# WX0_008_941DL.net
KiCad netlist of a schematic drawn in Altium Designer
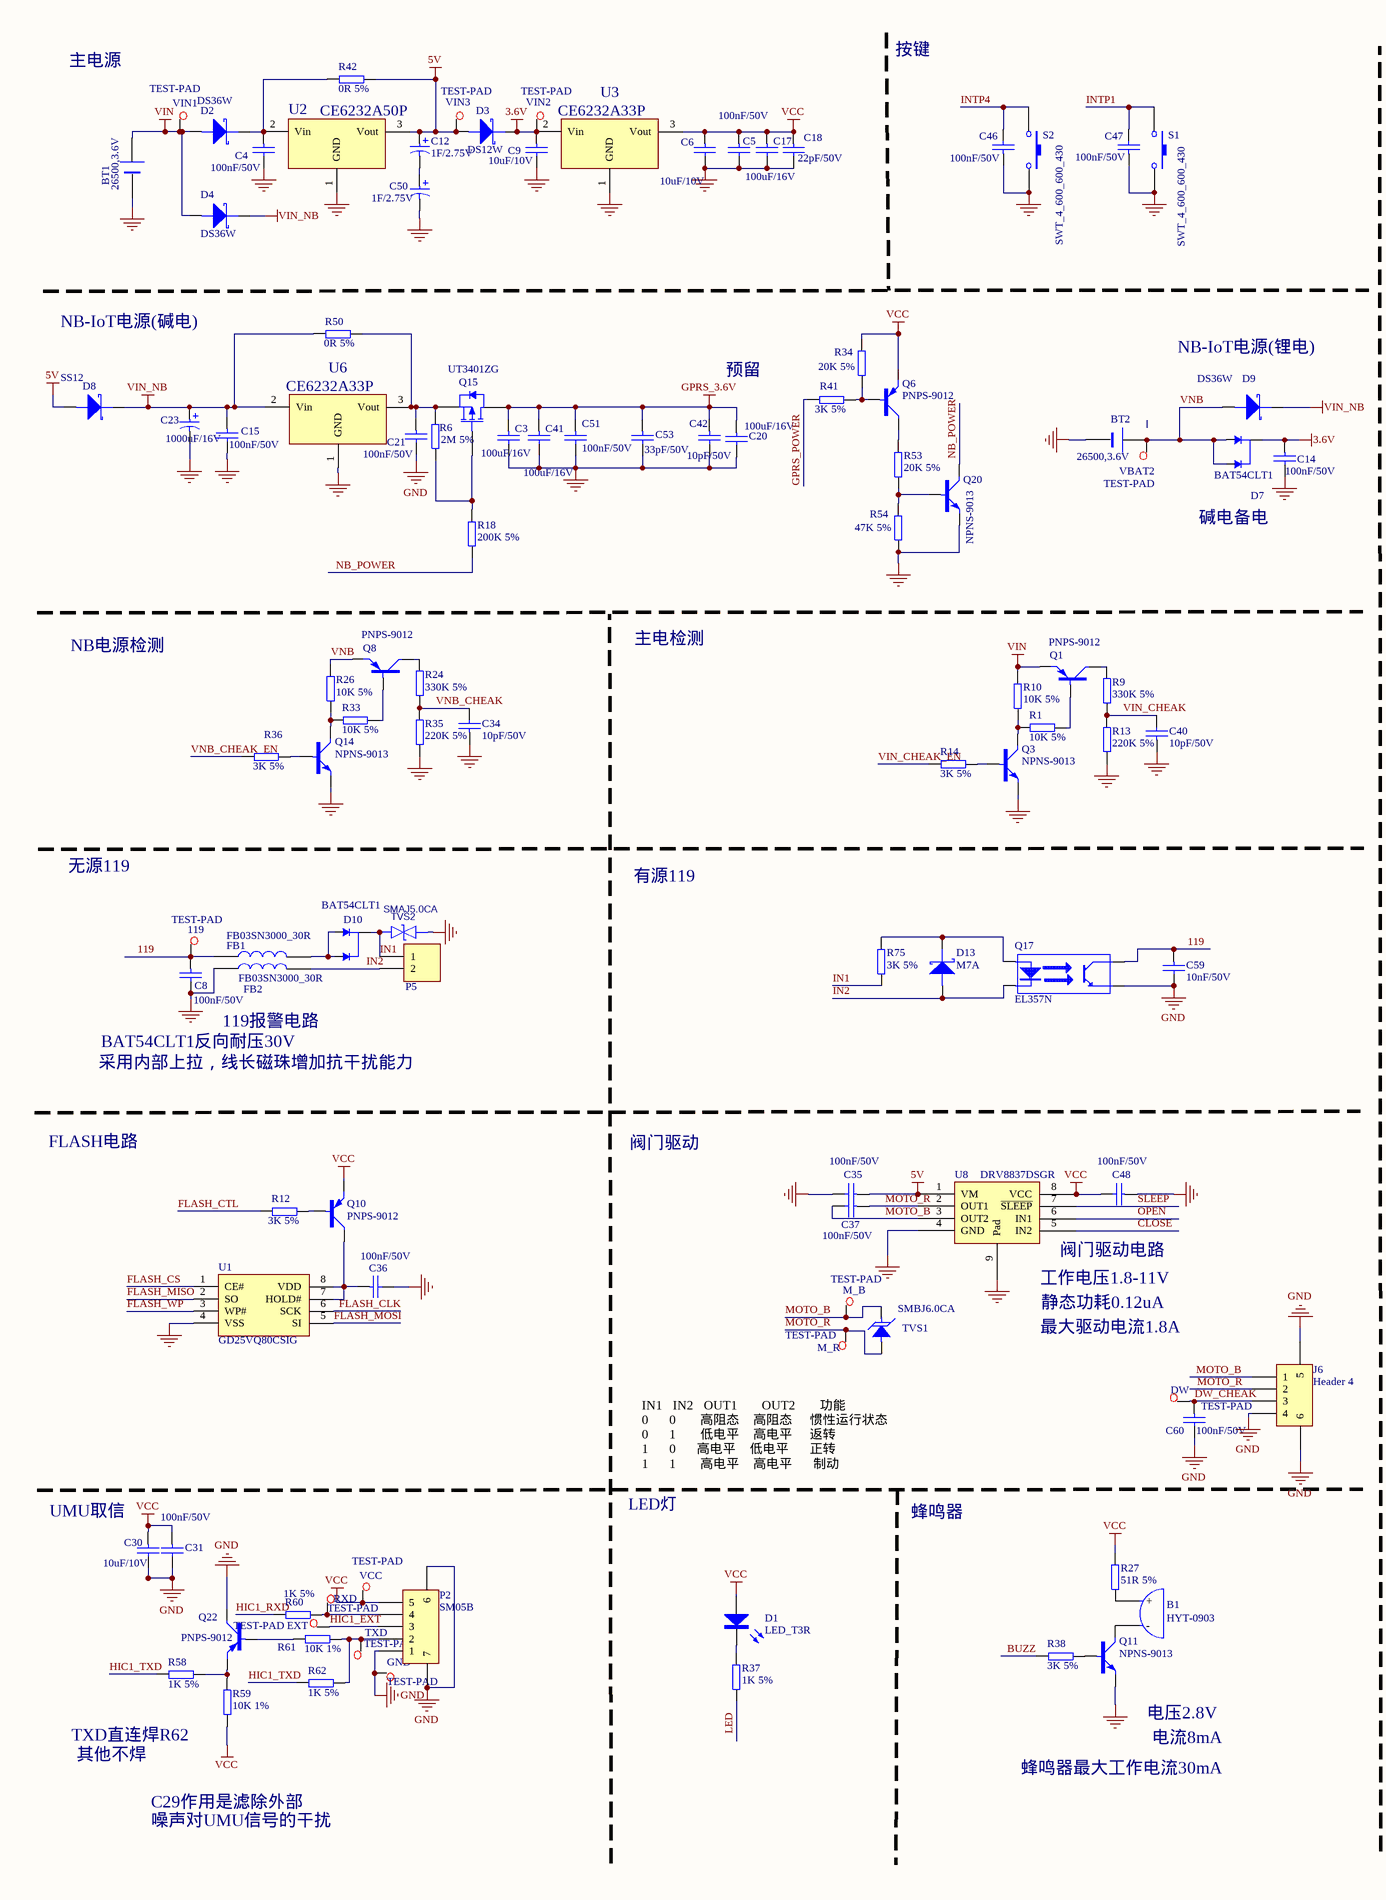
[diagram p0: WX0.008.941DL.SchDoc, left]
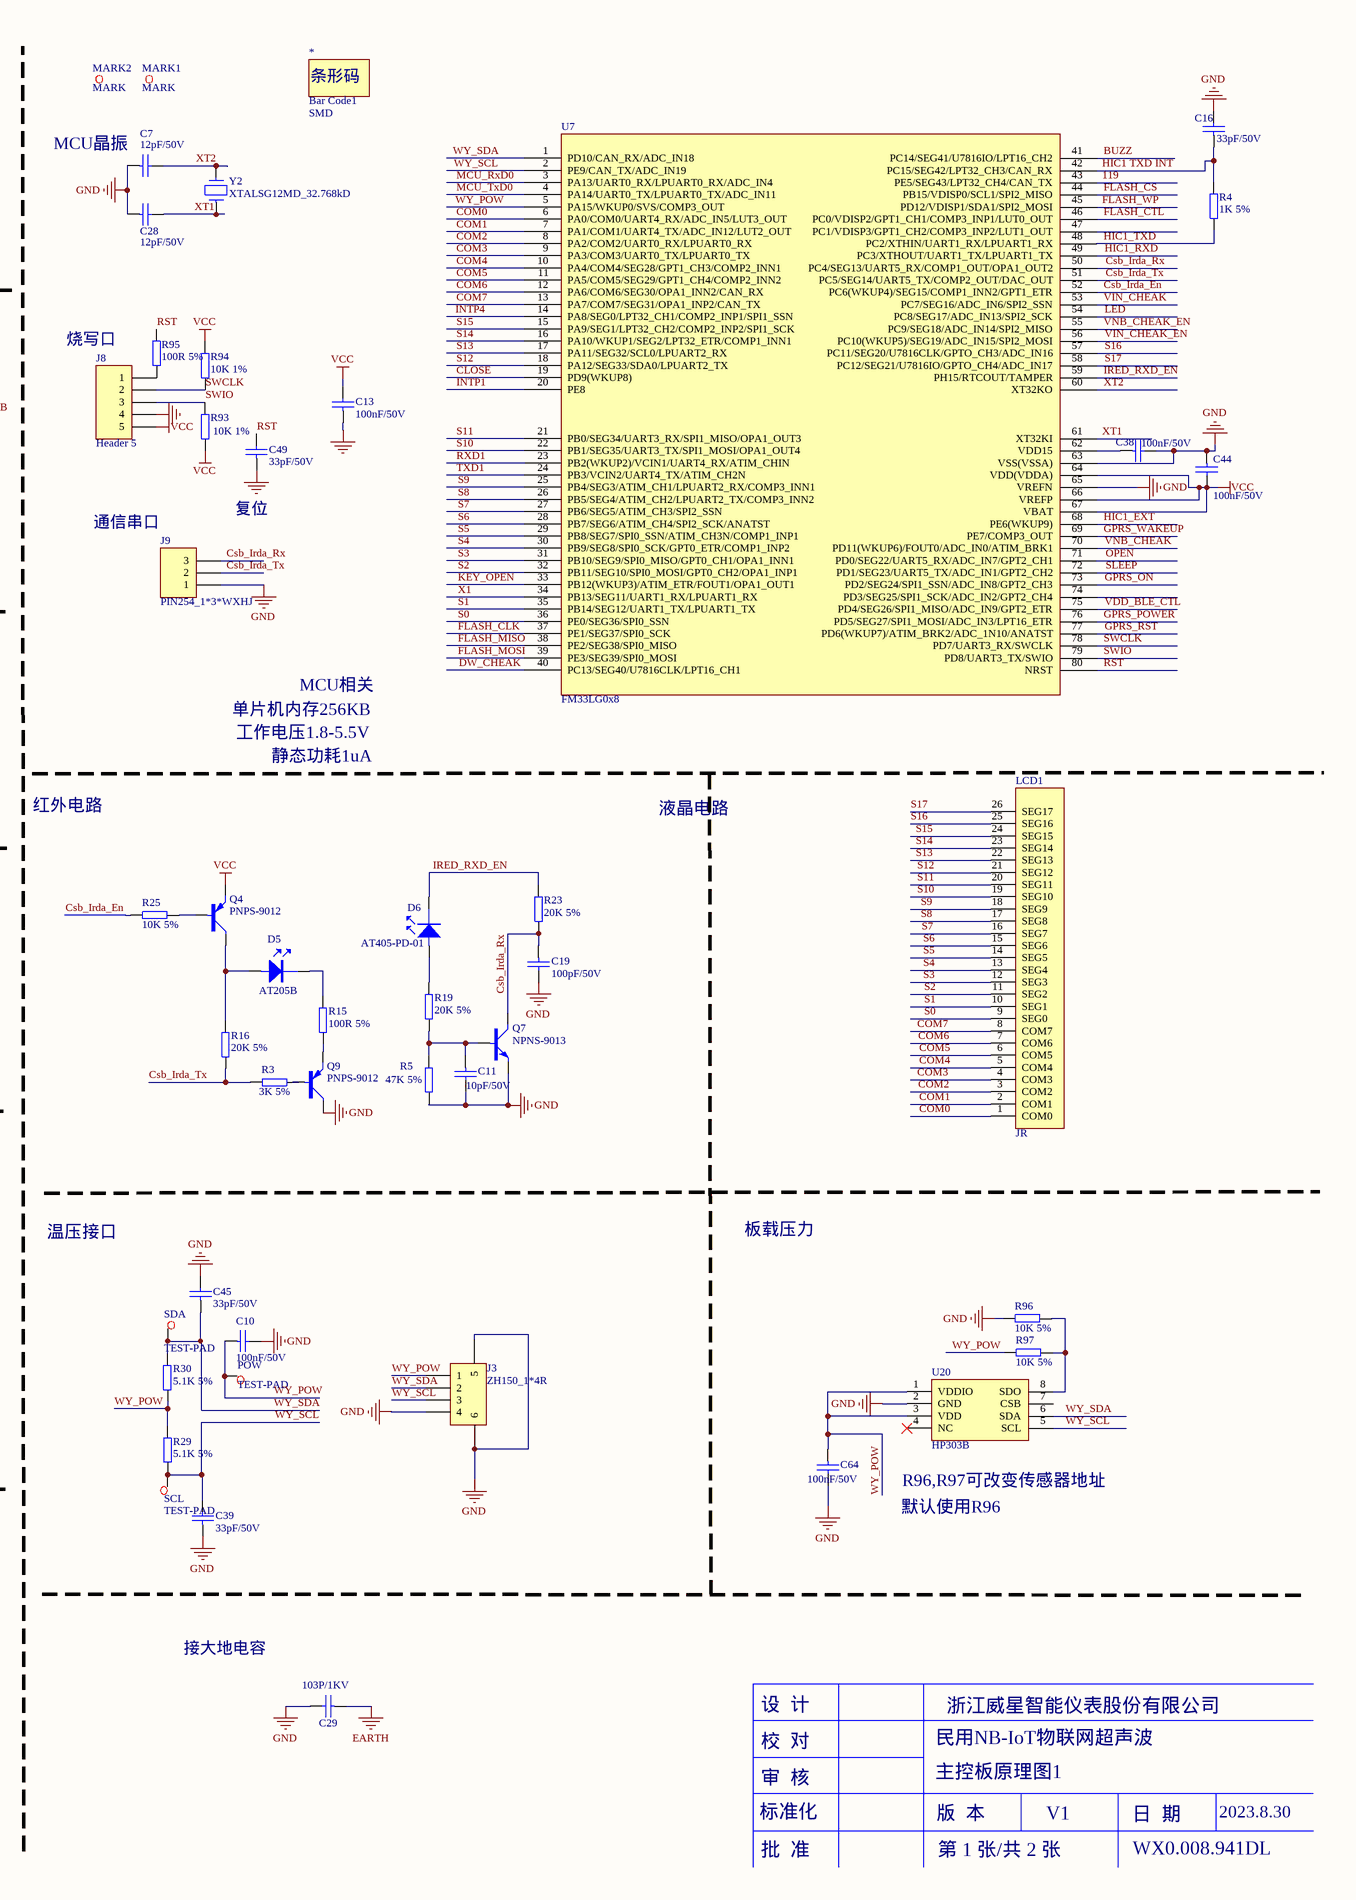
[diagram p1: WX0.008.941DL.SchDoc, right]

(export (version "E")
  (design (tool "Eeschema 10.0.6"))
  (components
    (comp (ref "*")
      (value "Bar Code1")
      (footprint "Bar Code1")
      (description "条形码 ,填充，无需焊接器件")
      (fields (field (name "PART NUMBER") "AD_WXHJ_Bar Code_02") (field (name "SMD/DIP") "SMD"))
      (libsource (lib "Database_Libs2") (part "05_AD_WXHJ_Bar Code_02"))
    )
    (comp (ref "119")
      (value "TEST-PAD")
      (footprint "TEST-PAD")
      (description "单面焊盘测试点")
      (fields (field (name "PART NUMBER") "AD_WXHJ_TEST-PAD_01"))
      (libsource (lib "Database_Libs2") (part "TEST-PAD"))
    )
    (comp (ref "B1")
      (value "HYT-0903")
      (footprint "HYT-0903")
      (description "直插,直径9mm,高5.5mm,5 V,2 V,30 mA,兴化市华宇电子有限公司,HYT-0903")
      (fields (field (name "PART NUMBER") "1010602-0007"))
      (libsource (lib "Database_Libs2") (part "07_HYT-0903"))
    )
    (comp (ref "BT1")
      (value "26500,3.6V")
      (footprint "BATFOOT")
      (description "Battery")
      (libsource (lib "*") (part "BATTERY_1"))
    )
    (comp (ref "BT2")
      (value "26500,3.6V")
      (footprint "BATFOOT")
      (description "Battery")
      (libsource (lib "*") (part "BATTERY_1"))
    )
    (comp (ref "C3")
      (value "100uF/16V")
      (footprint "GRM31CR60J107ME39L")
      (description "100u,16 V,±10%,1206,国巨,CC1206KRNPO7BN106P")
      (libsource (lib "Database_Libs2") (part "CC06KPO7_106P"))
    )
    (comp (ref "C4")
      (value "100nF/50V")
      (footprint "CAP0603")
      (description "104pF,50 V,±10%,0603,国巨,CC0603KRX7R9BB104")
      (fields (field (name "PART NUMBER") "101020103-0021"))
      (libsource (lib "Database_Libs2") (part "CC03K7R9_100N"))
    )
    (comp (ref "C5")
      (value "100nF/50V")
      (footprint "CAP0603")
      (description "104pF,50 V,±10%,0603,国巨,CC0603KRX7R9BB104")
      (fields (field (name "PART NUMBER") "101020103-0021"))
      (libsource (lib "Database_Libs2") (part "CC03K7R9_100N"))
    )
    (comp (ref "C6")
      (value "10uF/10V")
      (footprint "CAP0603")
      (description "106pF,10 V,±10%,0603,村田,GRM188R61A106KE47D")
      (fields (field (name "PART NUMBER") "101020103-0026"))
      (libsource (lib "Database_Libs2") (part "CC03K5R6_10U"))
    )
    (comp (ref "C7")
      (value "12pF/50V")
      (footprint "CAP0603")
      (description "12P,50 V,±5%,0603,国巨,CC0603JRNPO9BN12")
      (fields (field (name "PART NUMBER") "101020103-0005"))
      (libsource (lib "Database_Libs2") (part "CC03JPO9_12P"))
    )
    (comp (ref "C8")
      (value "100nF/50V")
      (footprint "CAP0603")
      (description "104pF,50 V,±10%,0603,国巨,CC0603KRX7R9BB104")
      (fields (field (name "PART NUMBER") "101020103-0021"))
      (libsource (lib "Database_Libs2") (part "CC03K7R9_100N"))
    )
    (comp (ref "C9")
      (value "10uF/10V")
      (footprint "CAP0603")
      (description "106pF,10 V,±10%,0603,村田,GRM188R61A106KE47D")
      (fields (field (name "PART NUMBER") "101020103-0026"))
      (libsource (lib "Database_Libs2") (part "CC03K5R6_10U"))
    )
    (comp (ref "C10")
      (value "100nF/50V")
      (footprint "CAP0603")
      (description "104pF,50 V,±10%,0603,国巨,CC0603KRX7R9BB104")
      (fields (field (name "PART NUMBER") "101020103-0021"))
      (libsource (lib "Database_Libs2") (part "CC03K7R9_100N"))
    )
    (comp (ref "C11")
      (value "10pF/50V")
      (footprint "CAP0603")
      (description "10pF,50 V,±5%,0603,X7R,国巨,CC0603JRNPO9BN100")
      (fields (field (name "PART NUMBER") "101020103-0014"))
      (libsource (lib "Database_Libs2") (part "CC03JPO9_10P"))
    )
    (comp (ref "C12")
      (value "1F/2.75V")
      (footprint "C-SUP-4P-H - L")
      (description "1F,2.75 V,-20%~+20%,8mm*16mm,红宝石,2.7 DMC 1 M MY4 8X16")
      (fields (field (name "PART NUMBER") "1010202-0015"))
      (libsource (lib "Database_Libs2") (part "CALM3MRDMC_1F"))
    )
    (comp (ref "C13")
      (value "100nF/50V")
      (footprint "CAP0603")
      (description "104pF,50 V,±10%,0603,国巨,CC0603KRX7R9BB104")
      (fields (field (name "PART NUMBER") "101020103-0021"))
      (libsource (lib "Database_Libs2") (part "CC03K7R9_100N"))
    )
    (comp (ref "C14")
      (value "100nF/50V")
      (footprint "CAP0603")
      (description "104pF,50 V,±10%,0603,国巨,CC0603KRX7R9BB104")
      (fields (field (name "PART NUMBER") "101020103-0021"))
      (libsource (lib "Database_Libs2") (part "CC03K7R9_100N"))
    )
    (comp (ref "C15")
      (value "100nF/50V")
      (footprint "CAP0603")
      (description "104pF,50 V,±10%,0603,国巨,CC0603KRX7R9BB104")
      (fields (field (name "PART NUMBER") "101020103-0021"))
      (libsource (lib "Database_Libs2") (part "CC03K7R9_100N"))
    )
    (comp (ref "C16")
      (value "33pF/50V")
      (footprint "CAP0603")
      (description "33pF,50 V,±10%,0603,国巨,CC0603KRNPO9BN33")
      (fields (field (name "PART NUMBER") "101020103-0027"))
      (libsource (lib "Database_Libs2") (part "CC03KPO9_33P"))
    )
    (comp (ref "C17")
      (value "100uF/16V")
      (footprint "GRM31CR60J107ME39L")
      (description "100u,16 V,±10%,1206,国巨,CC1206KRNPO7BN106P")
      (libsource (lib "Database_Libs2") (part "CC06KPO7_106P"))
    )
    (comp (ref "C18")
      (value "22pF/50V")
      (footprint "CAP0603")
      (description "22pF,50 V,±5%,0603,国巨,CC0603JRNPO9BN22")
      (fields (field (name "PART NUMBER") "101020103-0009"))
      (libsource (lib "Database_Libs2") (part "CC03JPO9_22P"))
    )
    (comp (ref "C19")
      (value "100pF/50V")
      (footprint "CAP0603")
      (description "101pf,50 V,±5%,0603,国巨,CC0603JRNP09BN101")
      (fields (field (name "PART NUMBER") "101020103-0010"))
      (libsource (lib "Database_Libs2") (part "CC03JPO9_101P"))
    )
    (comp (ref "C20")
      (value "100uF/16V")
      (footprint "GRM31CR60J107ME39L")
      (libsource (lib "Database_Libs2") (part "CC06KPO7_106P"))
    )
    (comp (ref "C21")
      (value "100nF/50V")
      (footprint "CAP0603")
      (description "104pF,50 V,±10%,0603,国巨,CC0603KRX7R9BB104")
      (fields (field (name "PART NUMBER") "101020103-0021"))
      (libsource (lib "Database_Libs2") (part "CC03K7R9_100N"))
    )
    (comp (ref "C23")
      (value "1000uF/16V")
      (footprint "CAPPC_500_800_2000R")
      (description "1000UF,16V,±20%,贴片10*10.2MM,深圳市三炎科电子科技有限公司,16V1000UF")
      (fields (field (name "PART NUMBER") "1010203-0026"))
      (libsource (lib "Database_Libs2") (part "CAL7MRZLH_1000U_R"))
    )
    (comp (ref "C28")
      (value "12pF/50V")
      (footprint "CAP0603")
      (description "12P,50 V,±5%,0603,国巨,CC0603JRNPO9BN12")
      (fields (field (name "PART NUMBER") "101020103-0005"))
      (libsource (lib "Database_Libs2") (part "CC03JPO9_12P"))
    )
    (comp (ref "C29")
      (value "103P/1KV")
      (footprint "CAP1206")
      (description "103P/1KV,±10％,1206")
      (fields (field (name "PART NUMBER") "101020101-0003"))
      (libsource (lib "altium-import") (part "root_3_CC03K7R9_100N_"))
    )
    (comp (ref "C30")
      (value "10uF/10V")
      (footprint "CAP0603")
      (description "106pF,10 V,±10%,0603,村田,GRM188R61A106KE47D")
      (fields (field (name "PART NUMBER") "101020103-0026"))
      (libsource (lib "Database_Libs2") (part "CC03K5R6_10U"))
    )
    (comp (ref "C31")
      (value "100nF/50V")
      (footprint "CAP0603")
      (description "104pF,50 V,±10%,0603,国巨,CC0603KRX7R9BB104")
      (fields (field (name "PART NUMBER") "101020103-0021"))
      (libsource (lib "Database_Libs2") (part "CC03K7R9_100N"))
    )
    (comp (ref "C34")
      (value "10pF/50V")
      (footprint "CAP0603")
      (description "10pF,50 V,±5%,0603,X7R,国巨,CC0603JRNPO9BN100")
      (fields (field (name "PART NUMBER") "101020103-0014"))
      (libsource (lib "Database_Libs2") (part "CC03JPO9_10P"))
    )
    (comp (ref "C35")
      (value "100nF/50V")
      (footprint "CAP0603")
      (description "104pF,50 V,±10%,0603,国巨,CC0603KRX7R9BB104")
      (fields (field (name "PART NUMBER") "101020103-0021"))
      (libsource (lib "Database_Libs2") (part "CC03K7R9_100N"))
    )
    (comp (ref "C36")
      (value "100nF/50V")
      (footprint "CAP0603")
      (description "104pF,50 V,±10%,0603,国巨,CC0603KRX7R9BB104")
      (fields (field (name "PART NUMBER") "101020103-0021"))
      (libsource (lib "Database_Libs2") (part "CC03K7R9_100N"))
    )
    (comp (ref "C37")
      (value "100nF/50V")
      (footprint "CAP0603")
      (description "104pF,50 V,±10%,0603,国巨,CC0603KRX7R9BB104")
      (fields (field (name "PART NUMBER") "101020103-0021"))
      (libsource (lib "Database_Libs2") (part "CC03K7R9_100N"))
    )
    (comp (ref "C38")
      (value "100nF/50V")
      (footprint "CAP0603")
      (description "104pF,50 V,±10%,0603,国巨,CC0603KRX7R9BB104")
      (fields (field (name "PART NUMBER") "101020103-0021"))
      (libsource (lib "Database_Libs2") (part "CC03K7R9_100N"))
    )
    (comp (ref "C39")
      (value "33pF/50V")
      (footprint "CAP0603")
      (description "33pF,50 V,±10%,0603,国巨,CC0603KRNPO9BN33")
      (fields (field (name "PART NUMBER") "101020103-0027"))
      (libsource (lib "Database_Libs2") (part "CC03KPO9_33P"))
    )
    (comp (ref "C40")
      (value "10pF/50V")
      (footprint "CAP0603")
      (description "10pF,50 V,±5%,0603,X7R,国巨,CC0603JRNPO9BN100")
      (fields (field (name "PART NUMBER") "101020103-0014"))
      (libsource (lib "Database_Libs2") (part "CC03JPO9_10P"))
    )
    (comp (ref "C41")
      (value "100uF/16V")
      (footprint "GRM31CR60J107ME39L")
      (description "100u,16 V,±10%,1206,国巨,CC1206KRNPO7BN106P")
      (libsource (lib "Database_Libs2") (part "CC06KPO7_106P"))
    )
    (comp (ref "C42")
      (value "10pF/50V")
      (footprint "CAP0603")
      (description "10pF,50 V,±5%,0603,X7R,国巨,CC0603JRNPO9BN100")
      (fields (field (name "PART NUMBER") "101020103-0014"))
      (libsource (lib "Database_Libs2") (part "CC03JPO9_10P"))
    )
    (comp (ref "C44")
      (value "100nF/50V")
      (footprint "CAP0603")
      (description "104pF,50 V,±10%,0603,国巨,CC0603KRX7R9BB104")
      (fields (field (name "PART NUMBER") "101020103-0021"))
      (libsource (lib "Database_Libs2") (part "CC03K7R9_100N"))
    )
    (comp (ref "C45")
      (value "33pF/50V")
      (footprint "CAP0603")
      (description "33pF,50 V,±10%,0603,国巨,CC0603KRNPO9BN33")
      (fields (field (name "PART NUMBER") "101020103-0027"))
      (libsource (lib "Database_Libs2") (part "CC03KPO9_33P"))
    )
    (comp (ref "C46")
      (value "100nF/50V")
      (footprint "CAP0603")
      (description "104pF,50 V,±10%,0603,国巨,CC0603KRX7R9BB104")
      (fields (field (name "PART NUMBER") "101020103-0021"))
      (libsource (lib "Database_Libs2") (part "CC03K7R9_100N"))
    )
    (comp (ref "C47")
      (value "100nF/50V")
      (footprint "CAP0603")
      (description "104pF,50 V,±10%,0603,国巨,CC0603KRX7R9BB104")
      (fields (field (name "PART NUMBER") "101020103-0021"))
      (libsource (lib "Database_Libs2") (part "CC03K7R9_100N"))
    )
    (comp (ref "C48")
      (value "100nF/50V")
      (footprint "CAP0603")
      (description "104pF,50 V,±10%,0603,国巨,CC0603KRX7R9BB104")
      (fields (field (name "PART NUMBER") "101020103-0021"))
      (libsource (lib "Database_Libs2") (part "CC03K7R9_100N"))
    )
    (comp (ref "C49")
      (value "33pF/50V")
      (footprint "CAP0603")
      (description "33pF,50 V,±10%,0603,国巨,CC0603KRNPO9BN33")
      (fields (field (name "PART NUMBER") "101020103-0027"))
      (libsource (lib "Database_Libs2") (part "CC03KPO9_33P"))
    )
    (comp (ref "C50")
      (value "1F/2.75V")
      (footprint "C-SUP-4P-H - L")
      (description "1F,2.75 V,-20%~+20%,8mm*16mm,红宝石,2.7 DMC 1 M MY4 8X16")
      (fields (field (name "PART NUMBER") "1010202-0015"))
      (libsource (lib "Database_Libs2") (part "CALM3MRDMC_1F"))
    )
    (comp (ref "C51")
      (value "100nF/50V")
      (footprint "CAP0603")
      (description "104pF,50 V,±10%,0603,国巨,CC0603KRX7R9BB104")
      (fields (field (name "PART NUMBER") "101020103-0021"))
      (libsource (lib "Database_Libs2") (part "CC03K7R9_100N"))
    )
    (comp (ref "C53")
      (value "33pF/50V")
      (footprint "CAP0603")
      (description "33pF,50 V,±10%,0603,国巨,CC0603KRNPO9BN33")
      (fields (field (name "PART NUMBER") "101020103-0027"))
      (libsource (lib "Database_Libs2") (part "CC03KPO9_33P"))
    )
    (comp (ref "C59")
      (value "10nF/50V")
      (footprint "CAP0603")
      (description "10nF,50 V,±10%,0603,X7R,国巨,CC0603KRX7R9BB103")
      (fields (field (name "PART NUMBER") "101020103-0007"))
      (libsource (lib "Database_Libs2") (part "CC03K7R9_103P"))
    )
    (comp (ref "C60")
      (value "100nF/50V")
      (footprint "CAP0603")
      (description "104pF,50 V,±10%,0603,国巨,CC0603KRX7R9BB104")
      (fields (field (name "PART NUMBER") "101020103-0021"))
      (libsource (lib "Database_Libs2") (part "CC03K7R9_100N"))
    )
    (comp (ref "C64")
      (value "100nF/50V")
      (footprint "CAP0603")
      (description "104pF,50 V,±10%,0603,国巨,CC0603KRX7R9BB104")
      (fields (field (name "PART NUMBER") "101020103-0021"))
      (libsource (lib "Database_Libs2") (part "CC03K7R9_100N"))
    )
    (comp (ref "D1")
      (value "LED_T3R")
      (footprint "LED3")
      (description "圆形插件,3mm 圆形,插件,红光,湖北匡通电子有限公司,3BB4HC")
      (fields (field (name "PART NUMBER") "101040102-0001"))
      (libsource (lib "Database_Libs2") (part "01-LED_T3R"))
    )
    (comp (ref "D2")
      (value "DS36W")
      (footprint "SOD-123FL")
      (description "DS36W,SOD123-FL,3 A,42 V,60 V,浙江领晨科技有限公司,DS36W")
      (fields (field (name "PART NUMBER") "101040101-0055"))
      (libsource (lib "Database_Libs2") (part "02_DS12W"))
    )
    (comp (ref "D3")
      (value "DS12W")
      (footprint "SOD-123FL")
      (description "DS12W,SOD-123FL,1 A,0.55 V,20 V,领晨科技,DS12W")
      (fields (field (name "PART NUMBER") "101040101-0048"))
      (libsource (lib "Database_Libs2") (part "02_DS12W"))
    )
    (comp (ref "D4")
      (value "DS36W")
      (footprint "SOD-123FL")
      (description "DS36W,SOD123-FL,3 A,42 V,60 V,浙江领晨科技有限公司,DS36W")
      (fields (field (name "PART NUMBER") "101040101-0055"))
      (libsource (lib "Database_Libs2") (part "02_DS36W"))
    )
    (comp (ref "D5")
      (value "AT205B")
      (footprint "IR_254_1000_500")
      (description "直插,Φ5.8mm圆头透明色，,0.1 A,4 V,5 V,上海品观电子有限公司,AT205B")
      (fields (field (name "PART NUMBER") "101040101-0034"))
      (libsource (lib "Database_Libs2") (part "01_AT205B"))
    )
    (comp (ref "D6")
      (value "AT405-PD-01")
      (footprint "IR_254_1000_500")
      (description "Φ5.8mm圆头黑色，光电接收管,Φ5.8mm,0.01 A,1.2 V,60 V,上海品观电子,AT405-PD-01")
      (fields (field (name "PART NUMBER") "101040101-0035"))
      (libsource (lib "Database_Libs2") (part "01_AT405-PD-01"))
    )
    (comp (ref "D7")
      (value "BAT54CLT1")
      (footprint "SOT-23")
      (description "BAT54CLT1，SOT23-3,SOT23-3,0.2 A,0.8 V,30 V,安森美,BAT54CLT1")
      (fields (field (name "PART NUMBER") "101040101-0038"))
      (libsource (lib "Database_Libs2") (part "02_BAT54CLT1"))
    )
    (comp (ref "D8")
      (value "SS12")
      (footprint "DO-214AC")
      (description "SS12,DO-214AC,1 A,0.55 V,20 V,昶鑫,SS12")
      (fields (field (name "PART NUMBER") "101040101-0009"))
      (libsource (lib "Database_Libs2") (part "02_SS12"))
    )
    (comp (ref "D9")
      (value "DS36W")
      (footprint "SOD-123FL")
      (description "DS36W,SOD123-FL,3 A,42 V,60 V,浙江领晨科技有限公司,DS36W")
      (fields (field (name "PART NUMBER") "101040101-0055"))
      (libsource (lib "Database_Libs2") (part "02_DS36W"))
    )
    (comp (ref "D10")
      (value "BAT54CLT1")
      (footprint "SOT-23")
      (description "BAT54CLT1，SOT23-3,SOT23-3,0.2 A,0.8 V,30 V,安森美,BAT54CLT1")
      (fields (field (name "PART NUMBER") "101040101-0038"))
      (libsource (lib "Database_Libs2") (part "02_BAT54CLT1"))
    )
    (comp (ref "D13")
      (value "M7A")
      (footprint "DO-214AC")
      (description "M7A,DO-214AC,1 A,1.1 V,1000 V,杭州闽达电子有限公司,M7A")
      (fields (field (name "PART NUMBER") "101040101-0008"))
      (libsource (lib "Database_Libs2") (part "02_M7A"))
    )
    (comp (ref "DW")
      (value "TEST-PAD")
      (footprint "TEST-PAD")
      (description "单面焊盘测试点")
      (fields (field (name "PART NUMBER") "AD_WXHJ_TEST-PAD_01"))
      (libsource (lib "Database_Libs2") (part "TEST-PAD"))
    )
    (comp (ref "EXT")
      (value "TEST-PAD")
      (footprint "TEST-PAD")
      (description "单面焊盘测试点")
      (fields (field (name "PART NUMBER") "AD_WXHJ_TEST-PAD_01"))
      (libsource (lib "Database_Libs2") (part "TEST-PAD"))
    )
    (comp (ref "FB1")
      (value "FB03SN3000_30R")
      (footprint "IND0603")
      (description "chilisin(奇力新),0603,30Ω ±25% @100MHz,150 V,125 ℃,PBY160808T-300Y-N,-55 ℃,不含铅,,,圆盘,30Ω ±25% @100MHz")
      (fields (field (name "PART NUMBER") "109010101-0003"))
      (libsource (lib "Database_Libs2") (part "06_FB03SN3000_30R"))
    )
    (comp (ref "FB2")
      (value "FB03SN3000_30R")
      (footprint "IND0603")
      (description "chilisin(奇力新),0603,30Ω ±25% @100MHz,150 V,125 ℃,PBY160808T-300Y-N,-55 ℃,不含铅,,,圆盘,30Ω ±25% @100MHz")
      (fields (field (name "PART NUMBER") "109010101-0003"))
      (libsource (lib "Database_Libs2") (part "06_FB03SN3000_30R"))
    )
    (comp (ref "GND")
      (value "TEST-PAD")
      (footprint "TEST-PAD")
      (description "单面焊盘测试点")
      (fields (field (name "PART NUMBER") "AD_WXHJ_TEST-PAD_01"))
      (libsource (lib "Database_Libs2") (part "TEST-PAD"))
    )
    (comp (ref "J3")
      (value "ZH150_1*4R")
      (footprint "SMT-1.5-4")
      (description "4针1.5mm间距，贴片卧式,9.0mm*6.5mm,公头,单排,4针1.5mm间距，贴片卧式")
      (fields (field (name "PART NUMBER") "1010902-0126"))
      (libsource (lib "Database_Libs2") (part "ZH150_1*4R"))
    )
    (comp (ref "J6")
      (value "Header 4")
      (footprint "SMT-1.5-4")
      (description "Header, 4-Pin")
      (fields (field (name "PUBLISHER") "Altium Limited"))
      (libsource (lib "WX0.000.514") (part "Header 4"))
    )
    (comp (ref "J8")
      (value "Header 5")
      (footprint "PIN254_1*5SR")
      (description "Header, 5-Pin")
      (libsource (lib "CBB_Lib_SCH") (part "Header 5"))
    )
    (comp (ref "J9")
      (value "PIN254_1*3*WXHJ")
      (footprint "PIN254_1*3*WXHJ")
      (description "1*3 ，Φ1.0 ，2.54mm，直脚,无需焊接器件")
      (fields (field (name "PART NUMBER") "AD_WXHJ_PinHeader_04"))
      (libsource (lib "Database_Libs2") (part "PIN254_1*3*WXHJ"))
    )
    (comp (ref "LCD1") (value "JR") (footprint "PCBComponent_1") (libsource (lib "未添加") (part "JR")))
    (comp (ref "MARK1")
      (value "MARK")
      (footprint "MARK")
      (description "MARK点")
      (fields (field (name "PART NUMBER") "AD_WXHJ_MARK_01"))
      (libsource (lib "Database_Libs2") (part "MARK"))
    )
    (comp (ref "MARK2")
      (value "MARK")
      (footprint "MARK")
      (description "MARK点")
      (fields (field (name "PART NUMBER") "AD_WXHJ_MARK_01"))
      (libsource (lib "Database_Libs2") (part "MARK"))
    )
    (comp (ref "M_B")
      (value "TEST-PAD")
      (footprint "TEST-PAD")
      (description "单面焊盘测试点")
      (fields (field (name "PART NUMBER") "AD_WXHJ_TEST-PAD_01"))
      (libsource (lib "Database_Libs2") (part "TEST-PAD"))
    )
    (comp (ref "M_R")
      (value "TEST-PAD")
      (footprint "TEST-PAD")
      (description "单面焊盘测试点")
      (fields (field (name "PART NUMBER") "AD_WXHJ_TEST-PAD_01"))
      (libsource (lib "Database_Libs2") (part "TEST-PAD"))
    )
    (comp (ref "P2") (value "SM05B") (footprint "SMT-1.25-5") (libsource (lib "Connect_WX") (part "SM05B")))
    (comp (ref "P5")
      (value "90 mm    WX100.060.LJ")
      (footprint "WXHJ_Connect_01")
      (description "电源连接线")
      (fields (field (name "PART NUMBER") "AD_WXHJ_Connect_01"))
      (libsource (lib "Database_Libs2") (part "WXHJ_Connect_01"))
    )
    (comp (ref "POW")
      (value "TEST-PAD")
      (footprint "TEST-PAD")
      (description "单面焊盘测试点")
      (fields (field (name "PART NUMBER") "AD_WXHJ_TEST-PAD_01"))
      (libsource (lib "Database_Libs2") (part "TEST-PAD"))
    )
    (comp (ref "Q1")
      (value "PNPS-9012")
      (footprint "SOT-23")
      (description "9012,PNP,SOT-23,JCET;长电,S9012")
      (fields (field (name "PART NUMBER") "101040201-0001"))
      (libsource (lib "Database_Libs2") (part "03_PNPS-9012"))
    )
    (comp (ref "Q3")
      (value "NPNS-9013")
      (footprint "SOT-23")
      (description "9013,NPN,SOT-23,长电,S9013")
      (fields (field (name "PART NUMBER") "101040201-0002"))
      (libsource (lib "Database_Libs2") (part "03_NPNS-9013"))
    )
    (comp (ref "Q4")
      (value "PNPS-9012")
      (footprint "SOT-23")
      (description "9012,PNP,SOT-23,JCET;长电,S9012")
      (fields (field (name "PART NUMBER") "101040201-0001"))
      (libsource (lib "Database_Libs2") (part "03_PNPS-9012"))
    )
    (comp (ref "Q6")
      (value "PNPS-9012")
      (footprint "SOT-23")
      (description "9012,PNP,SOT-23,JCET;长电,S9012")
      (fields (field (name "PART NUMBER") "101040201-0001"))
      (libsource (lib "Database_Libs2") (part "03_PNPS-9012"))
    )
    (comp (ref "Q7")
      (value "NPNS-9013")
      (footprint "SOT-23")
      (description "9013,NPN,SOT-23,长电,S9013")
      (fields (field (name "PART NUMBER") "101040201-0002"))
      (libsource (lib "Database_Libs2") (part "03_NPNS-9013"))
    )
    (comp (ref "Q8")
      (value "PNPS-9012")
      (footprint "SOT-23")
      (description "9012,PNP,SOT-23,JCET;长电,S9012")
      (fields (field (name "PART NUMBER") "101040201-0001"))
      (libsource (lib "Database_Libs2") (part "03_PNPS-9012"))
    )
    (comp (ref "Q9")
      (value "PNPS-9012")
      (footprint "SOT-23")
      (description "9012,PNP,SOT-23,JCET;长电,S9012")
      (fields (field (name "PART NUMBER") "101040201-0001"))
      (libsource (lib "Database_Libs2") (part "03_PNPS-9012"))
    )
    (comp (ref "Q10")
      (value "PNPS-9012")
      (footprint "SOT-23")
      (description "9012,PNP,SOT-23,JCET;长电,S9012")
      (fields (field (name "PART NUMBER") "101040201-0001"))
      (libsource (lib "Database_Libs2") (part "03_PNPS-9012"))
    )
    (comp (ref "Q11")
      (value "NPNS-9013")
      (footprint "SOT-23")
      (description "9013,NPN,SOT-23,长电,S9013")
      (fields (field (name "PART NUMBER") "101040201-0002"))
      (libsource (lib "Database_Libs2") (part "03_NPNS-9013"))
    )
    (comp (ref "Q14")
      (value "NPNS-9013")
      (footprint "SOT-23")
      (description "9013,NPN,SOT-23,长电,S9013")
      (fields (field (name "PART NUMBER") "101040201-0002"))
      (libsource (lib "Database_Libs2") (part "03_NPNS-9013"))
    )
    (comp (ref "Q15")
      (value "UT3401ZG")
      (footprint "SOT-23")
      (description "UT3401ZG,P-MOS,SOT-23,UTC,UT3401ZG")
      (fields (field (name "PART NUMBER") "101040201-0013"))
      (libsource (lib "Database_Libs2") (part "03_P-UT3401ZG"))
    )
    (comp (ref "Q17")
      (value "EL357N")
      (footprint "EL357D")
      (description "SOP4,贴片,ELERLIGHT,EL357N(D)(TA)-G")
      (fields (field (name "PART NUMBER") "1010502-0045"))
      (libsource (lib "Database_Libs2") (part "01_EL357N9(D)(TA)-G"))
    )
    (comp (ref "Q20")
      (value "NPNS-9013")
      (footprint "SOT-23")
      (description "9013,NPN,SOT-23,长电,S9013")
      (fields (field (name "PART NUMBER") "101040201-0002"))
      (libsource (lib "Database_Libs2") (part "03_NPNS-9013"))
    )
    (comp (ref "Q22")
      (value "PNPS-9012")
      (footprint "SOT-23")
      (description "9012,PNP,SOT-23,JCET;长电,S9012")
      (fields (field (name "PART NUMBER") "101040201-0001"))
      (libsource (lib "Database_Libs2") (part "03_PNPS-9012"))
    )
    (comp (ref "R1")
      (value "10K 5%")
      (footprint "RES0603")
      (description "国巨,±5%,0603,,155 ℃,-55 ℃,RC0603JR-0710KL,无铅,200 ppm/℃,1/10W,,10K")
      (fields (field (name "PART NUMBER") "101010103-0003"))
      (libsource (lib "Database_Libs2") (part "RC03J_10K"))
    )
    (comp (ref "R3")
      (value "3K 5%")
      (footprint "RES0603")
      (description "国巨,±5%,0603,,155 ℃,-55 ℃,RC0603JR-073KL,无铅,100 ppm/℃,1/10W,,3K")
      (fields (field (name "PART NUMBER") "101010103-0006"))
      (libsource (lib "Database_Libs2") (part "RC03J_3K"))
    )
    (comp (ref "R4")
      (value "1K 5%")
      (footprint "RES0603")
      (description "1K,±5%,1/10W,0603,国巨,RC0603JR-071KL")
      (fields (field (name "PART NUMBER") "101010103-0008"))
      (libsource (lib "Database_Libs2") (part "RC03J_1K"))
    )
    (comp (ref "R5")
      (value "47K 5%")
      (footprint "RES0603")
      (description "47K,±5%,1/10W,0603,国巨,RC0603JR-0747KL")
      (fields (field (name "PART NUMBER") "101010103-0012"))
      (libsource (lib "Database_Libs2") (part "RC03J_47K"))
    )
    (comp (ref "R6")
      (value "2M 5%")
      (footprint "RES0603")
      (description "国巨,±5%,0603,,155 ℃,-55 ℃,RC0603JR-072ML,含铅,100 ppm/℃,1/10W,,2M")
      (fields (field (name "PART NUMBER") "101010103-0025"))
      (libsource (lib "Database_Libs2") (part "RC03J_2M"))
    )
    (comp (ref "R9")
      (value "330K 5%")
      (footprint "RES0603")
      (description "330K,±5%,1/10W,0603,国巨,RC0603JR-07330KL")
      (fields (field (name "PART NUMBER") "101010103-0066"))
      (libsource (lib "Database_Libs2") (part "RC03J_330K"))
    )
    (comp (ref "R10")
      (value "10K 5%")
      (footprint "RES0603")
      (description "国巨,±5%,0603,,155 ℃,-55 ℃,RC0603JR-0710KL,无铅,200 ppm/℃,1/10W,,10K")
      (fields (field (name "PART NUMBER") "101010103-0003"))
      (libsource (lib "Database_Libs2") (part "RC03J_10K"))
    )
    (comp (ref "R12")
      (value "3K 5%")
      (footprint "RES0603")
      (description "国巨,±5%,0603,,155 ℃,-55 ℃,RC0603JR-073KL,无铅,100 ppm/℃,1/10W,,3K")
      (fields (field (name "PART NUMBER") "101010103-0006"))
      (libsource (lib "Database_Libs2") (part "RC03J_3K"))
    )
    (comp (ref "R13")
      (value "220K 5%")
      (footprint "RES0603")
      (description "220K,±5%,1/10W,0603,国巨,RC0603JR-07220KL")
      (fields (field (name "PART NUMBER") "101010103-0044"))
      (libsource (lib "Database_Libs2") (part "RC03J_220K"))
    )
    (comp (ref "R14")
      (value "3K 5%")
      (footprint "RES0603")
      (description "国巨,±5%,0603,,155 ℃,-55 ℃,RC0603JR-073KL,无铅,100 ppm/℃,1/10W,,3K")
      (fields (field (name "PART NUMBER") "101010103-0006"))
      (libsource (lib "Database_Libs2") (part "RC03J_3K"))
    )
    (comp (ref "R15")
      (value "100R 5%")
      (footprint "RES0603")
      (description "100R,±5%,1/10W,0603,国巨,RC0603JR-07100RL")
      (fields (field (name "PART NUMBER") "101010103-0022"))
      (libsource (lib "Database_Libs2") (part "RC03J_100R"))
    )
    (comp (ref "R16")
      (value "20K 5%")
      (footprint "RES0603")
      (description "国巨,±5%,0603,,155 ℃,-55 ℃,RC0603JR-0720KL,无铅,200 ppm/℃,1/10W,,20K")
      (fields (field (name "PART NUMBER") "101010103-0004"))
      (libsource (lib "Database_Libs2") (part "RC03J_20K"))
    )
    (comp (ref "R18")
      (value "200K 5%")
      (footprint "RES0603")
      (description "200K,±5%,1/10W,0603,国巨,RC0603JR-07200KL")
      (fields (field (name "PART NUMBER") "101010103-0034"))
      (libsource (lib "Database_Libs2") (part "RC03J_200K"))
    )
    (comp (ref "R19")
      (value "20K 5%")
      (footprint "RES0603")
      (description "国巨,±5%,0603,,155 ℃,-55 ℃,RC0603JR-0720KL,无铅,200 ppm/℃,1/10W,,20K")
      (fields (field (name "PART NUMBER") "101010103-0004"))
      (libsource (lib "Database_Libs2") (part "RC03J_20K"))
    )
    (comp (ref "R23")
      (value "20K 5%")
      (footprint "RES0603")
      (description "国巨,±5%,0603,,155 ℃,-55 ℃,RC0603JR-0720KL,无铅,200 ppm/℃,1/10W,,20K")
      (fields (field (name "PART NUMBER") "101010103-0004"))
      (libsource (lib "Database_Libs2") (part "RC03J_20K"))
    )
    (comp (ref "R24")
      (value "330K 5%")
      (footprint "RES0603")
      (description "330K,±5%,1/10W,0603,国巨,RC0603JR-07330KL")
      (fields (field (name "PART NUMBER") "101010103-0066"))
      (libsource (lib "Database_Libs2") (part "RC03J_330K"))
    )
    (comp (ref "R25")
      (value "10K 5%")
      (footprint "RES0603")
      (description "国巨,±5%,0603,,155 ℃,-55 ℃,RC0603JR-0710KL,无铅,200 ppm/℃,1/10W,,10K")
      (fields (field (name "PART NUMBER") "101010103-0003"))
      (libsource (lib "Database_Libs2") (part "RC03J_10K"))
    )
    (comp (ref "R26")
      (value "10K 5%")
      (footprint "RES0603")
      (description "国巨,±5%,0603,,155 ℃,-55 ℃,RC0603JR-0710KL,无铅,200 ppm/℃,1/10W,,10K")
      (fields (field (name "PART NUMBER") "101010103-0003"))
      (libsource (lib "Database_Libs2") (part "RC03J_10K"))
    )
    (comp (ref "R27")
      (value "51R 5%")
      (footprint "RES0603")
      (description "国巨,±5%,0603,,155 ℃,-55 ℃,RC0603JR-0751RL,无铅,100 ppm/℃,1/10W,,51欧")
      (fields (field (name "PART NUMBER") "101010103-0037"))
      (libsource (lib "Database_Libs2") (part "RC03J_51R"))
    )
    (comp (ref "R29")
      (value "5.1K 5%")
      (footprint "RES0603")
      (description "国巨,±5%,0603,,155 ℃,55 ℃,RC0603JR-075.1KL,无铅,200 ppm/℃,1/10W,,5.1k")
      (fields (field (name "PART NUMBER") "101010103-0015"))
      (libsource (lib "Database_Libs2") (part "RC03J_5.1K"))
    )
    (comp (ref "R30")
      (value "5.1K 5%")
      (footprint "RES0603")
      (description "国巨,±5%,0603,,155 ℃,55 ℃,RC0603JR-075.1KL,无铅,200 ppm/℃,1/10W,,5.1k")
      (fields (field (name "PART NUMBER") "101010103-0015"))
      (libsource (lib "Database_Libs2") (part "RC03J_5.1K"))
    )
    (comp (ref "R33")
      (value "10K 5%")
      (footprint "RES0603")
      (description "国巨,±5%,0603,,155 ℃,-55 ℃,RC0603JR-0710KL,无铅,200 ppm/℃,1/10W,,10K")
      (fields (field (name "PART NUMBER") "101010103-0003"))
      (libsource (lib "Database_Libs2") (part "RC03J_10K"))
    )
    (comp (ref "R34")
      (value "20K 5%")
      (footprint "RES0603")
      (description "国巨,±5%,0603,,155 ℃,-55 ℃,RC0603JR-0720KL,无铅,200 ppm/℃,1/10W,,20K")
      (fields (field (name "PART NUMBER") "101010103-0004"))
      (libsource (lib "Database_Libs2") (part "RC03J_20K"))
    )
    (comp (ref "R35")
      (value "220K 5%")
      (footprint "RES0603")
      (description "220K,±5%,1/10W,0603,国巨,RC0603JR-07220KL")
      (fields (field (name "PART NUMBER") "101010103-0044"))
      (libsource (lib "Database_Libs2") (part "RC03J_220K"))
    )
    (comp (ref "R36")
      (value "3K 5%")
      (footprint "RES0603")
      (description "国巨,±5%,0603,,155 ℃,-55 ℃,RC0603JR-073KL,无铅,100 ppm/℃,1/10W,,3K")
      (fields (field (name "PART NUMBER") "101010103-0006"))
      (libsource (lib "Database_Libs2") (part "RC03J_3K"))
    )
    (comp (ref "R37")
      (value "1K 5%")
      (footprint "RES0603")
      (description "1K,±5%,1/10W,0603,国巨,RC0603JR-071KL")
      (fields (field (name "PART NUMBER") "101010103-0008"))
      (libsource (lib "Database_Libs2") (part "RC03J_1K"))
    )
    (comp (ref "R38")
      (value "3K 5%")
      (footprint "RES0603")
      (description "国巨,±5%,0603,,155 ℃,-55 ℃,RC0603JR-073KL,无铅,100 ppm/℃,1/10W,,3K")
      (fields (field (name "PART NUMBER") "101010103-0006"))
      (libsource (lib "Database_Libs2") (part "RC03J_3K"))
    )
    (comp (ref "R41")
      (value "3K 5%")
      (footprint "RES0603")
      (description "国巨,±5%,0603,,155 ℃,-55 ℃,RC0603JR-073KL,无铅,100 ppm/℃,1/10W,,3K")
      (fields (field (name "PART NUMBER") "101010103-0006"))
      (libsource (lib "Database_Libs2") (part "RC03J_3K"))
    )
    (comp (ref "R42")
      (value "0R 5%")
      (footprint "RES1206")
      (description "0Ω,±5%,1/4W,1206,国巨,RC1206JR-070RL")
      (fields (field (name "PART NUMBER") "101010101-0013"))
      (libsource (lib "Database_Libs2") (part "RC06J_0R"))
    )
    (comp (ref "R50")
      (value "0R 5%")
      (footprint "RES1206")
      (description "0Ω,±5%,1/4W,1206,国巨,RC1206JR-070RL")
      (fields (field (name "PART NUMBER") "101010101-0013"))
      (libsource (lib "Database_Libs2") (part "RC06J_0R"))
    )
    (comp (ref "R53")
      (value "20K 5%")
      (footprint "RES0603")
      (description "国巨,±5%,0603,,155 ℃,-55 ℃,RC0603JR-0720KL,无铅,200 ppm/℃,1/10W,,20K")
      (fields (field (name "PART NUMBER") "101010103-0004"))
      (libsource (lib "Database_Libs2") (part "RC03J_20K"))
    )
    (comp (ref "R54")
      (value "47K 5%")
      (footprint "RES0603")
      (description "47K,±5%,1/10W,0603,国巨,RC0603JR-0747KL")
      (fields (field (name "PART NUMBER") "101010103-0012"))
      (libsource (lib "Database_Libs2") (part "RC03J_47K"))
    )
    (comp (ref "R58")
      (value "1K 5%")
      (footprint "RES0603")
      (description "1K,±5%,1/10W,0603,国巨,RC0603JR-071KL")
      (fields (field (name "PART NUMBER") "101010103-0008"))
      (libsource (lib "Database_Libs2") (part "RC03J_1K"))
    )
    (comp (ref "R59")
      (value "10K 1%")
      (footprint "RES0603")
      (description "10K±1%,1/10W,0603")
      (fields (field (name "PART NUMBER") "101010103-0052"))
      (libsource (lib "Database_Libs2") (part "RC03J_10K"))
    )
    (comp (ref "R60")
      (value "1K 5%")
      (footprint "RES0603")
      (description "1K,±5%,1/10W,0603,国巨,RC0603JR-071KL")
      (fields (field (name "PART NUMBER") "101010103-0008"))
      (libsource (lib "Database_Libs2") (part "RC03J_1K"))
    )
    (comp (ref "R61")
      (value "10K 1%")
      (footprint "RES0603")
      (description "10K±1%,1/10W,0603")
      (fields (field (name "PART NUMBER") "101010103-0052"))
      (libsource (lib "Database_Libs2") (part "RC03J_10K"))
    )
    (comp (ref "R62")
      (value "1K 5%")
      (footprint "RES0603")
      (description "1K,±5%,1/10W,0603,国巨,RC0603JR-071KL")
      (fields (field (name "PART NUMBER") "101010103-0008"))
      (libsource (lib "Database_Libs2") (part "RC03J_1K"))
    )
    (comp (ref "R75")
      (value "3K 5%")
      (footprint "RES0603")
      (description "国巨,±5%,0603,,155 ℃,-55 ℃,RC0603JR-073KL,无铅,100 ppm/℃,1/10W,,3K")
      (fields (field (name "PART NUMBER") "101010103-0006"))
      (libsource (lib "Database_Libs2") (part "RC03J_3K"))
    )
    (comp (ref "R93")
      (value "10K 1%")
      (footprint "RES0603")
      (description "10K±1%,1/10W,0603")
      (fields (field (name "PART NUMBER") "101010103-0052"))
      (libsource (lib "Database_Libs2") (part "RC03J_10K"))
    )
    (comp (ref "R94")
      (value "10K 1%")
      (footprint "RES0603")
      (description "10K±1%,1/10W,0603")
      (fields (field (name "PART NUMBER") "101010103-0052"))
      (libsource (lib "Database_Libs2") (part "RC03J_10K"))
    )
    (comp (ref "R95")
      (value "100R 5%")
      (footprint "RES0603")
      (description "100R,±5%,1/10W,0603,国巨,RC0603JR-07100RL")
      (fields (field (name "PART NUMBER") "101010103-0022"))
      (libsource (lib "Database_Libs2") (part "RC03J_100R"))
    )
    (comp (ref "R96")
      (value "10K 5%")
      (footprint "RES0603")
      (description "国巨,±5%,0603,,155 ℃,-55 ℃,RC0603JR-071ML,无铅,200 ppm/℃,1/10W,,1M")
      (fields (field (name "PART NUMBER") "101010103-0002"))
      (libsource (lib "Database_Libs2") (part "RC03J_1M"))
    )
    (comp (ref "R97")
      (value "10K 5%")
      (footprint "RES0603")
      (description "国巨,±5%,0603,,155 ℃,-55 ℃,RC0603JR-071ML,无铅,200 ppm/℃,1/10W,,1M")
      (fields (field (name "PART NUMBER") "101010103-0002"))
      (libsource (lib "Database_Libs2") (part "RC03J_1M"))
    )
    (comp (ref "RXD")
      (value "TEST-PAD")
      (footprint "TEST-PAD")
      (description "单面焊盘测试点")
      (fields (field (name "PART NUMBER") "AD_WXHJ_TEST-PAD_01"))
      (libsource (lib "Database_Libs2") (part "TEST-PAD"))
    )
    (comp (ref "S1")
      (value "SWT_4_600_600_430")
      (footprint "SW-KEY")
      (description "TS-1102,机械轻触,6*6*4.3直插,6*6*4.3直插,乐清市羽欧电子")
      (fields (field (name "PART NUMBER") "1011001-0027"))
      (libsource (lib "Database_Libs2") (part "07_SWT_4_600_600_430"))
    )
    (comp (ref "S2")
      (value "SWT_4_600_600_430")
      (footprint "SW-KEY")
      (description "TS-1102,机械轻触,6*6*4.3直插,6*6*4.3直插,乐清市羽欧电子")
      (fields (field (name "PART NUMBER") "1011001-0027"))
      (libsource (lib "Database_Libs2") (part "07_SWT_4_600_600_430"))
    )
    (comp (ref "SCL")
      (value "TEST-PAD")
      (footprint "TEST-PAD")
      (description "单面焊盘测试点")
      (fields (field (name "PART NUMBER") "AD_WXHJ_TEST-PAD_01"))
      (libsource (lib "Database_Libs2") (part "TEST-PAD"))
    )
    (comp (ref "SDA")
      (value "TEST-PAD")
      (footprint "TEST-PAD")
      (description "单面焊盘测试点")
      (fields (field (name "PART NUMBER") "AD_WXHJ_TEST-PAD_01"))
      (libsource (lib "Database_Libs2") (part "TEST-PAD"))
    )
    (comp (ref "TVS1")
      (value "SMBJ6.0CA")
      (footprint "DO-214AA")
      (description "SMBJ6.0CA,DO-214AA,10.3 V,6.0 V,600 W,58.3 A,800 uA,上海君耀电子有限公司,SMBJ6.0CA")
      (fields (field (name "PART NUMBER") "101040101-0024"))
      (libsource (lib "Database_Libs2") (part "05_SMBJ6.0CA"))
    )
    (comp (ref "TVS2")
      (value "SMAJ5.0CA")
      (footprint "SMAJ5.0CA")
      (fields (field (name "BOM_SUPPLIER PART") "C693487") (field (name "CONTRIBUTOR") "LCSC"))
      (libsource (lib "Discrete_WX") (part "SMAJ5.0CA_C693487"))
    )
    (comp (ref "TXD")
      (value "TEST-PAD")
      (footprint "TEST-PAD")
      (description "单面焊盘测试点")
      (fields (field (name "PART NUMBER") "AD_WXHJ_TEST-PAD_01"))
      (libsource (lib "Database_Libs2") (part "TEST-PAD"))
    )
    (comp (ref "U1")
      (value "GD25VQ80CSIG")
      (footprint "SOP-8L-200MIL")
      (description "GD25VQ80CSIG,SOP8 208mil,北京兆易创新科技股份有限公司,GD25VQ80CSIG")
      (fields (field (name "PART NUMBER") "101050101-0165"))
      (libsource (lib "Database_Libs2") (part "04_GD25VQ80CSIG"))
    )
    (comp (ref "U2")
      (value "CE6232A50P")
      (footprint "SOT-89")
      (fields (field (name "PART NUMBER") "1010503-0013"))
      (libsource (lib "Database_Libs2") (part "02_S-1206B50-U3"))
    )
    (comp (ref "U3")
      (value "CE6232A33P")
      (footprint "SOT-89")
      (fields (field (name "PART NUMBER") "1010503-0002"))
      (libsource (lib "Database_Libs2") (part "02_S-1206B33-U3T1G"))
    )
    (comp (ref "U6")
      (value "CE6232A33P")
      (footprint "SOT-89")
      (fields (field (name "PART NUMBER") "1010503-0002"))
      (libsource (lib "Database_Libs2") (part "02_S-1206B33-U3T1G"))
    )
    (comp (ref "U7") (value "FM33LG0x8") (footprint "LQFP80") (libsource (lib "FM_MCU") (part "FM33LG0x8")))
    (comp (ref "U8")
      (value "DRV8837DSGR")
      (footprint "S-PWSON-N8")
      (description "DRV8837DSGR,S-PWSON-N8,TI,DRV8837DSGR")
      (fields (field (name "PART NUMBER") "101050101-0060"))
      (libsource (lib "Database_Libs2") (part "07_DRV8837DSGR"))
    )
    (comp (ref "U20") (value "HP303B") (footprint "LGA_8") (libsource (lib "Schlib2") (part "HP303B")))
    (comp (ref "VBAT2")
      (value "TEST-PAD")
      (footprint "TEST-PAD")
      (description "单面焊盘测试点")
      (fields (field (name "PART NUMBER") "AD_WXHJ_TEST-PAD_01"))
      (libsource (lib "Database_Libs2") (part "TEST-PAD"))
    )
    (comp (ref "VCC")
      (value "TEST-PAD")
      (footprint "TEST-PAD")
      (description "单面焊盘测试点")
      (fields (field (name "PART NUMBER") "AD_WXHJ_TEST-PAD_01"))
      (libsource (lib "Database_Libs2") (part "TEST-PAD"))
    )
    (comp (ref "VIN1")
      (value "TEST-PAD")
      (footprint "TEST-PAD")
      (description "单面焊盘测试点")
      (fields (field (name "PART NUMBER") "AD_WXHJ_TEST-PAD_01"))
      (libsource (lib "Database_Libs2") (part "TEST-PAD"))
    )
    (comp (ref "VIN2")
      (value "TEST-PAD")
      (footprint "TEST-PAD")
      (description "单面焊盘测试点")
      (fields (field (name "PART NUMBER") "AD_WXHJ_TEST-PAD_01"))
      (libsource (lib "Database_Libs2") (part "TEST-PAD"))
    )
    (comp (ref "VIN3")
      (value "TEST-PAD")
      (footprint "TEST-PAD")
      (description "单面焊盘测试点")
      (fields (field (name "PART NUMBER") "AD_WXHJ_TEST-PAD_01"))
      (libsource (lib "Database_Libs2") (part "TEST-PAD"))
    )
    (comp (ref "Y2")
      (value "XTALSG12MD_32.768kD")
      (footprint "SMD-3215_2P")
      (fields (field (name "PART NUMBER") "1010601-0009"))
      (libsource (lib "Database_Libs2") (part "04_XTALSG12MD_32.768kD"))
    )
  )
  (nets
    (net (code "1") (name "/119") (class "Default")
      (node (ref "119") (pin "1") (pinfunction "1_1") (pintype "passive"))
      (node (ref "C59") (pin "1") (pinfunction "1_1") (pintype "passive"))
      (node (ref "C8") (pin "1") (pinfunction "1_1") (pintype "passive"))
      (node (ref "FB1") (pin "1") (pinfunction "1_1") (pintype "passive"))
      (node (ref "Q17") (pin "4") (pintype "passive"))
      (node (ref "U7") (pin "43") (pinfunction "PE5/SEG43/LPT32_CH4/CAN_TX_43") (pintype "passive"))
    )
    (net (code "2") (name "/BUZZ") (class "Default")
      (node (ref "R38") (pin "1") (pinfunction "1_1") (pintype "passive"))
      (node (ref "U7") (pin "41") (pinfunction "PC14/SEG41/U7816IO/LPT16_CH2_41") (pintype "passive"))
    )
    (net (code "3") (name "/CLOSE") (class "Default")
      (node (ref "U7") (pin "19") (pinfunction "PD9(WKUP8)_19") (pintype "passive"))
      (node (ref "U8") (pin "5") (pinfunction "IN2_5") (pintype "passive"))
    )
    (net (code "4") (name "/COM0") (class "Default")
      (node (ref "LCD1") (pin "1") (pinfunction "COM0_1") (pintype "passive"))
      (node (ref "U7") (pin "6") (pinfunction "PA0/COM0/UART4_RX/ADC_IN5/LUT3_OUT_6") (pintype "passive"))
    )
    (net (code "5") (name "/COM1") (class "Default")
      (node (ref "LCD1") (pin "2") (pinfunction "COM1_2") (pintype "passive"))
      (node (ref "U7") (pin "7") (pinfunction "PA1/COM1/UART4_TX/ADC_IN12/LUT2_OUT_7") (pintype "passive"))
    )
    (net (code "6") (name "/COM2") (class "Default")
      (node (ref "LCD1") (pin "3") (pinfunction "COM2_3") (pintype "passive"))
      (node (ref "U7") (pin "8") (pinfunction "PA2/COM2/UART0_RX/LPUART0_RX_8") (pintype "passive"))
    )
    (net (code "7") (name "/COM3") (class "Default")
      (node (ref "LCD1") (pin "4") (pinfunction "COM3_4") (pintype "passive"))
      (node (ref "U7") (pin "9") (pinfunction "PA3/COM3/UART0_TX/LPUART0_TX_9") (pintype "passive"))
    )
    (net (code "8") (name "/COM4") (class "Default")
      (node (ref "LCD1") (pin "5") (pinfunction "COM4_5") (pintype "passive"))
      (node (ref "U7") (pin "10") (pinfunction "PA4/COM4/SEG28/GPT1_CH3/COMP2_INN1_10") (pintype "passive"))
    )
    (net (code "9") (name "/COM5") (class "Default")
      (node (ref "LCD1") (pin "6") (pinfunction "COM5_6") (pintype "passive"))
      (node (ref "U7") (pin "11") (pinfunction "PA5/COM5/SEG29/GPT1_CH4/COMP2_INN2_11") (pintype "passive"))
    )
    (net (code "10") (name "/COM6") (class "Default")
      (node (ref "LCD1") (pin "7") (pinfunction "COM6_7") (pintype "passive"))
      (node (ref "U7") (pin "12") (pinfunction "PA6/COM6/SEG30/OPA1_INN2/CAN_RX_12") (pintype "passive"))
    )
    (net (code "11") (name "/COM7") (class "Default")
      (node (ref "LCD1") (pin "8") (pinfunction "COM7_8") (pintype "passive"))
      (node (ref "U7") (pin "13") (pinfunction "PA7/COM7/SEG31/OPA1_INP2/CAN_TX_13") (pintype "passive"))
    )
    (net (code "12") (name "/Csb_Irda_En") (class "Default")
      (node (ref "R25") (pin "2") (pinfunction "2_2") (pintype "passive"))
      (node (ref "U7") (pin "52") (pinfunction "PC6(WKUP4)/SEG15/COMP1_INN2/GPT1_ETR_52") (pintype "passive"))
    )
    (net (code "13") (name "/Csb_Irda_Rx") (class "Default")
      (node (ref "C19") (pin "1") (pinfunction "1_1") (pintype "passive"))
      (node (ref "J9") (pin "3") (pinfunction "3_3") (pintype "passive"))
      (node (ref "Q7") (pin "3") (pinfunction "C_3") (pintype "passive"))
      (node (ref "R23") (pin "1") (pinfunction "1_1") (pintype "passive"))
      (node (ref "U7") (pin "50") (pinfunction "PC4/SEG13/UART5_RX/COMP1_OUT/OPA1_OUT2_50") (pintype "passive"))
    )
    (net (code "14") (name "/Csb_Irda_Tx") (class "Default")
      (node (ref "J9") (pin "2") (pinfunction "2_2") (pintype "passive"))
      (node (ref "R16") (pin "1") (pinfunction "1_1") (pintype "passive"))
      (node (ref "R3") (pin "1") (pinfunction "1_1") (pintype "passive"))
      (node (ref "U7") (pin "51") (pinfunction "PC5/SEG14/UART5_TX/COMP2_OUT/DAC_OUT_51") (pintype "passive"))
    )
    (net (code "15") (name "/DW_CHEAK") (class "Default")
      (node (ref "C60") (pin "1") (pinfunction "1_1") (pintype "passive"))
      (node (ref "DW") (pin "1") (pinfunction "1_1") (pintype "passive"))
      (node (ref "J6") (pin "3") (pinfunction "3_3") (pintype "passive"))
      (node (ref "U7") (pin "40") (pinfunction "PC13/SEG40/U7816CLK/LPT16_CH1_40") (pintype "passive"))
    )
    (net (code "16") (name "/FLASH_CLK") (class "Default")
      (node (ref "U1") (pin "6") (pinfunction "SCK_6") (pintype "passive"))
      (node (ref "U7") (pin "37") (pinfunction "PE1/SEG37/SPI0_SCK_37") (pintype "passive"))
    )
    (net (code "17") (name "/FLASH_CS") (class "Default")
      (node (ref "U1") (pin "1") (pinfunction "CE#_1") (pintype "passive"))
      (node (ref "U7") (pin "44") (pinfunction "PB15/VDISP0/SCL1/SPI2_MISO_44") (pintype "passive"))
    )
    (net (code "18") (name "/FLASH_CTL") (class "Default")
      (node (ref "R12") (pin "1") (pinfunction "1_1") (pintype "passive"))
      (node (ref "U7") (pin "46") (pinfunction "PC0/VDISP2/GPT1_CH1/COMP3_INP1/LUT0_OUT_46") (pintype "passive"))
    )
    (net (code "19") (name "/FLASH_MISO") (class "Default")
      (node (ref "U1") (pin "2") (pinfunction "SO_2") (pintype "passive"))
      (node (ref "U7") (pin "38") (pinfunction "PE2/SEG38/SPI0_MISO_38") (pintype "passive"))
    )
    (net (code "20") (name "/FLASH_MOSI") (class "Default")
      (node (ref "U1") (pin "5") (pinfunction "SI_5") (pintype "passive"))
      (node (ref "U7") (pin "39") (pinfunction "PE3/SEG39/SPI0_MOSI_39") (pintype "passive"))
    )
    (net (code "21") (name "/FLASH_WP") (class "Default")
      (node (ref "U1") (pin "3") (pinfunction "WP#_3") (pintype "passive"))
      (node (ref "U7") (pin "45") (pinfunction "PD12/VDISP1/SDA1/SPI2_MOSI_45") (pintype "passive"))
    )
    (net (code "22") (name "/GPRS_ON") (class "Default")
      (node (ref "U7") (pin "73") (pinfunction "PD2/SEG24/SPI1_SSN/ADC_IN8/GPT2_CH3_73") (pintype "passive"))
    )
    (net (code "23") (name "/GPRS_POWER") (class "Default")
      (node (ref "R41") (pin "1") (pinfunction "1_1") (pintype "passive"))
      (node (ref "U7") (pin "76") (pinfunction "PD5/SEG27/SPI1_MOSI/ADC_IN3/LPT16_ETR_76") (pintype "passive"))
    )
    (net (code "24") (name "/GPRS_RST") (class "Default")
      (node (ref "U7") (pin "77") (pinfunction "PD6(WKUP7)/ATIM_BRK2/ADC_1N10/ANATST_77") (pintype "passive"))
    )
    (net (code "25") (name "/GPRS_WAKEUP") (class "Default")
      (node (ref "U7") (pin "69") (pinfunction "PE7/COMP3_OUT_69") (pintype "passive"))
    )
    (net (code "26") (name "/HIC1 TXD INT") (class "Default")
      (node (ref "C16") (pin "1") (pinfunction "1_1") (pintype "passive"))
      (node (ref "R4") (pin "2") (pinfunction "2_2") (pintype "passive"))
      (node (ref "U7") (pin "42") (pinfunction "PC15/SEG42/LPT32_CH3/CAN_RX_42") (pintype "passive"))
    )
    (net (code "27") (name "/HIC1_EXT") (class "Default")
      (node (ref "EXT") (pin "1") (pinfunction "1_1") (pintype "passive"))
      (node (ref "P2") (pin "3") (pinfunction "3_3") (pintype "passive"))
      (node (ref "U7") (pin "68") (pinfunction "PE6(WKUP9)_68") (pintype "passive"))
    )
    (net (code "28") (name "/HIC1_RXD") (class "Default")
      (node (ref "R60") (pin "1") (pinfunction "1_1") (pintype "passive"))
      (node (ref "U7") (pin "49") (pinfunction "PC3/XTHOUT/UART1_TX/LPUART1_TX_49") (pintype "passive"))
    )
    (net (code "29") (name "/HIC1_TXD") (class "Default")
      (node (ref "R4") (pin "1") (pinfunction "1_1") (pintype "passive"))
      (node (ref "R58") (pin "1") (pinfunction "1_1") (pintype "passive"))
      (node (ref "R62") (pin "1") (pinfunction "1_1") (pintype "passive"))
      (node (ref "U7") (pin "48") (pinfunction "PC2/XTHIN/UART1_RX/LPUART1_RX_48") (pintype "passive"))
    )
    (net (code "30") (name "/IN1") (class "Default")
      (node (ref "D10") (pin "3") (pinfunction "C_3") (pintype "passive"))
      (node (ref "P5") (pin "1") (pinfunction "1_1") (pintype "passive"))
      (node (ref "R75") (pin "1") (pinfunction "1_1") (pintype "passive"))
      (node (ref "TVS2") (pin "1") (pinfunction "1_1") (pintype "passive"))
    )
    (net (code "31") (name "/IN2") (class "Default")
      (node (ref "D13") (pin "1") (pinfunction "1_1") (pintype "passive"))
      (node (ref "FB2") (pin "2") (pinfunction "2_2") (pintype "passive"))
      (node (ref "P5") (pin "2") (pinfunction "2_2") (pintype "passive"))
      (node (ref "Q17") (pin "2") (pintype "passive"))
    )
    (net (code "32") (name "/INTP1") (class "Default")
      (node (ref "C47") (pin "2") (pinfunction "2_2") (pintype "passive"))
      (node (ref "S1") (pin "1") (pinfunction "1_1") (pintype "passive"))
      (node (ref "U7") (pin "20") (pinfunction "PE8_20") (pintype "passive"))
    )
    (net (code "33") (name "/INTP4") (class "Default")
      (node (ref "C46") (pin "2") (pinfunction "2_2") (pintype "passive"))
      (node (ref "S2") (pin "1") (pinfunction "1_1") (pintype "passive"))
      (node (ref "U7") (pin "14") (pinfunction "PA8/SEG0/LPT32_CH1/COMP2_INP1/SPI1_SSN_14") (pintype "passive"))
    )
    (net (code "34") (name "/IRED_RXD_EN") (class "Default")
      (node (ref "D6") (pin "2") (pinfunction "2_2") (pintype "passive"))
      (node (ref "R23") (pin "2") (pinfunction "2_2") (pintype "passive"))
      (node (ref "U7") (pin "59") (pinfunction "PH15/RTCOUT/TAMPER_59") (pintype "passive"))
    )
    (net (code "35") (name "/KEY_OPEN") (class "Default")
      (node (ref "U7") (pin "33") (pinfunction "PB12(WKUP3)/ATIM_ETR/FOUT1/OPA1_OUT1_33") (pintype "passive"))
    )
    (net (code "36") (name "/LED") (class "Default")
      (node (ref "R37") (pin "1") (pinfunction "1_1") (pintype "passive"))
      (node (ref "U7") (pin "54") (pinfunction "PC8/SEG17/ADC_IN13/SPI2_SCK_54") (pintype "passive"))
    )
    (net (code "37") (name "/MCU_RxD0") (class "Default")
      (node (ref "U7") (pin "3") (pinfunction "PA13/UART0_RX/LPUART0_RX/ADC_IN4_3") (pintype "passive"))
    )
    (net (code "38") (name "/MCU_TxD0") (class "Default")
      (node (ref "U7") (pin "4") (pinfunction "PA14/UART0_TX/LPUART0_TX/ADC_IN11_4") (pintype "passive"))
    )
    (net (code "39") (name "/MOTO_B") (class "Default")
      (node (ref "C37") (pin "2") (pinfunction "2_2") (pintype "passive"))
      (node (ref "J6") (pin "1") (pinfunction "1_1") (pintype "passive"))
      (node (ref "M_B") (pin "1") (pinfunction "1_1") (pintype "passive"))
      (node (ref "TVS1") (pin "2") (pinfunction "2_2") (pintype "passive"))
      (node (ref "U8") (pin "3") (pinfunction "OUT2_3") (pintype "passive"))
    )
    (net (code "40") (name "/MOTO_R") (class "Default")
      (node (ref "C37") (pin "1") (pinfunction "1_1") (pintype "passive"))
      (node (ref "J6") (pin "2") (pinfunction "2_2") (pintype "passive"))
      (node (ref "M_R") (pin "1") (pinfunction "1_1") (pintype "passive"))
      (node (ref "TVS1") (pin "1") (pinfunction "1_1") (pintype "passive"))
      (node (ref "U8") (pin "2") (pinfunction "OUT1_2") (pintype "passive"))
    )
    (net (code "41") (name "/NB_POWER") (class "Default")
      (node (ref "Q20") (pin "3") (pinfunction "C_3") (pintype "passive"))
      (node (ref "R18") (pin "1") (pinfunction "1_1") (pintype "passive"))
    )
    (net (code "42") (name "/OPEN") (class "Default")
      (node (ref "U7") (pin "71") (pinfunction "PD0/SEG22/UART5_RX/ADC_IN7/GPT2_CH1_71") (pintype "passive"))
      (node (ref "U8") (pin "6") (pinfunction "IN1_6") (pintype "passive"))
    )
    (net (code "43") (name "/RST") (class "Default")
      (node (ref "C49") (pin "2") (pinfunction "2_2") (pintype "passive"))
      (node (ref "R95") (pin "1") (pinfunction "1_1") (pintype "passive"))
      (node (ref "U7") (pin "80") (pinfunction "NRST_80") (pintype "passive"))
    )
    (net (code "44") (name "/RXD1") (class "Default")
      (node (ref "U7") (pin "23") (pinfunction "PB2(WKUP2)/VCIN1/UART4_RX/ATIM_CHIN_23") (pintype "passive"))
    )
    (net (code "45") (name "/S0") (class "Default")
      (node (ref "LCD1") (pin "9") (pinfunction "SEG0_9") (pintype "passive"))
      (node (ref "U7") (pin "36") (pinfunction "PE0/SEG36/SPI0_SSN_36") (pintype "passive"))
    )
    (net (code "46") (name "/S1") (class "Default")
      (node (ref "LCD1") (pin "10") (pinfunction "SEG1_10") (pintype "passive"))
      (node (ref "U7") (pin "35") (pinfunction "PB14/SEG12/UART1_TX/LPUART1_TX_35") (pintype "passive"))
    )
    (net (code "47") (name "/S2") (class "Default")
      (node (ref "LCD1") (pin "11") (pinfunction "SEG2_11") (pintype "passive"))
      (node (ref "U7") (pin "32") (pinfunction "PB11/SEG10/SPI0_MOSI/GPT0_CH2/OPA1_INP1_32") (pintype "passive"))
    )
    (net (code "48") (name "/S3") (class "Default")
      (node (ref "LCD1") (pin "12") (pinfunction "SEG3_12") (pintype "passive"))
      (node (ref "U7") (pin "31") (pinfunction "PB10/SEG9/SPI0_MISO/GPT0_CH1/OPA1_INN1_31") (pintype "passive"))
    )
    (net (code "49") (name "/S4") (class "Default")
      (node (ref "LCD1") (pin "13") (pinfunction "SEG4_13") (pintype "passive"))
      (node (ref "U7") (pin "30") (pinfunction "PB9/SEG8/SPI0_SCK/GPT0_ETR/COMP1_INP2_30") (pintype "passive"))
    )
    (net (code "50") (name "/S5") (class "Default")
      (node (ref "LCD1") (pin "14") (pinfunction "SEG5_14") (pintype "passive"))
      (node (ref "U7") (pin "29") (pinfunction "PB8/SEG7/SPI0_SSN/ATIM_CH3N/COMP1_INP1_29") (pintype "passive"))
    )
    (net (code "51") (name "/S6") (class "Default")
      (node (ref "LCD1") (pin "15") (pinfunction "SEG6_15") (pintype "passive"))
      (node (ref "U7") (pin "28") (pinfunction "PB7/SEG6/ATIM_CH4/SPI2_SCK/ANATST_28") (pintype "passive"))
    )
    (net (code "52") (name "/S7") (class "Default")
      (node (ref "LCD1") (pin "16") (pinfunction "SEG7_16") (pintype "passive"))
      (node (ref "U7") (pin "27") (pinfunction "PB6/SEG5/ATIM_CH3/SPI2_SSN_27") (pintype "passive"))
    )
    (net (code "53") (name "/S8") (class "Default")
      (node (ref "LCD1") (pin "17") (pinfunction "SEG8_17") (pintype "passive"))
      (node (ref "U7") (pin "26") (pinfunction "PB5/SEG4/ATIM_CH2/LPUART2_TX/COMP3_INN2_26") (pintype "passive"))
    )
    (net (code "54") (name "/S9") (class "Default")
      (node (ref "LCD1") (pin "18") (pinfunction "SEG9_18") (pintype "passive"))
      (node (ref "U7") (pin "25") (pinfunction "PB4/SEG3/ATIM_CH1/LPUART2_RX/COMP3_INN1_25") (pintype "passive"))
    )
    (net (code "55") (name "/S10") (class "Default")
      (node (ref "LCD1") (pin "19") (pinfunction "SEG10_19") (pintype "passive"))
      (node (ref "U7") (pin "22") (pinfunction "PB1/SEG35/UART3_TX/SPI1_MOSI/OPA1_OUT4_22") (pintype "passive"))
    )
    (net (code "56") (name "/S11") (class "Default")
      (node (ref "LCD1") (pin "20") (pinfunction "SEG11_20") (pintype "passive"))
      (node (ref "U7") (pin "21") (pinfunction "PB0/SEG34/UART3_RX/SPI1_MISO/OPA1_OUT3_21") (pintype "passive"))
    )
    (net (code "57") (name "/S12") (class "Default")
      (node (ref "LCD1") (pin "21") (pinfunction "SEG12_21") (pintype "passive"))
      (node (ref "U7") (pin "18") (pinfunction "PA12/SEG33/SDA0/LPUART2_TX_18") (pintype "passive"))
    )
    (net (code "58") (name "/S13") (class "Default")
      (node (ref "LCD1") (pin "22") (pinfunction "SEG13_22") (pintype "passive"))
      (node (ref "U7") (pin "17") (pinfunction "PA11/SEG32/SCL0/LPUART2_RX_17") (pintype "passive"))
    )
    (net (code "59") (name "/S14") (class "Default")
      (node (ref "LCD1") (pin "23") (pinfunction "SEG14_23") (pintype "passive"))
      (node (ref "U7") (pin "16") (pinfunction "PA10/WKUP1/SEG2/LPT32_ETR/COMP1_INN1_16") (pintype "passive"))
    )
    (net (code "60") (name "/S15") (class "Default")
      (node (ref "LCD1") (pin "24") (pinfunction "SEG15_24") (pintype "passive"))
      (node (ref "U7") (pin "15") (pinfunction "PA9/SEG1/LPT32_CH2/COMP2_INP2/SPI1_SCK_15") (pintype "passive"))
    )
    (net (code "61") (name "/S16") (class "Default")
      (node (ref "LCD1") (pin "25") (pinfunction "SEG16_25") (pintype "passive"))
      (node (ref "U7") (pin "57") (pinfunction "PC11/SEG20/U7816CLK/GPTO_CH3/ADC_IN16_57") (pintype "passive"))
    )
    (net (code "62") (name "/S17") (class "Default")
      (node (ref "LCD1") (pin "26") (pinfunction "SEG17_26") (pintype "passive"))
      (node (ref "U7") (pin "58") (pinfunction "PC12/SEG21/U7816IO/GPTO_CH4/ADC_IN17_58") (pintype "passive"))
    )
    (net (code "63") (name "/SLEEP") (class "Default")
      (node (ref "U7") (pin "72") (pinfunction "PD1/SEG23/UART5_TX/ADC_IN1/GPT2_CH2_72") (pintype "passive"))
      (node (ref "U8") (pin "7") (pinfunction "~{SLEEP}_7") (pintype "passive"))
    )
    (net (code "64") (name "/SWCLK") (class "Default")
      (node (ref "J8") (pin "2") (pinfunction "2_2") (pintype "passive"))
      (node (ref "R94") (pin "1") (pinfunction "1_1") (pintype "passive"))
      (node (ref "U7") (pin "78") (pinfunction "PD7/UART3_RX/SWCLK_78") (pintype "passive"))
    )
    (net (code "65") (name "/SWIO") (class "Default")
      (node (ref "J8") (pin "3") (pinfunction "3_3") (pintype "passive"))
      (node (ref "R93") (pin "2") (pinfunction "2_2") (pintype "passive"))
      (node (ref "U7") (pin "79") (pinfunction "PD8/UART3_TX/SWIO_79") (pintype "passive"))
    )
    (net (code "66") (name "/TXD1") (class "Default")
      (node (ref "U7") (pin "24") (pinfunction "PB3/VCIN2/UART4_TX/ATIM_CH2N_24") (pintype "passive"))
    )
    (net (code "67") (name "/VDD_BLE_CTL") (class "Default")
      (node (ref "U7") (pin "75") (pinfunction "PD4/SEG26/SPI1_MISO/ADC_IN9/GPT2_ETR_75") (pintype "passive"))
    )
    (net (code "68") (name "/VIN_CHEAK") (class "Default")
      (node (ref "C40") (pin "2") (pinfunction "2_2") (pintype "passive"))
      (node (ref "R13") (pin "1") (pinfunction "1_1") (pintype "passive"))
      (node (ref "R9") (pin "2") (pinfunction "2_2") (pintype "passive"))
      (node (ref "U7") (pin "53") (pinfunction "PC7/SEG16/ADC_IN6/SPI2_SSN_53") (pintype "passive"))
    )
    (net (code "69") (name "/VIN_CHEAK_EN") (class "Default")
      (node (ref "R14") (pin "1") (pinfunction "1_1") (pintype "passive"))
      (node (ref "U7") (pin "56") (pinfunction "PC10(WKUP5)/SEG19/ADC_IN15/SPI2_MOSI_56") (pintype "passive"))
    )
    (net (code "70") (name "/VNB") (class "Default")
      (node (ref "BT2") (pin "1") (pinfunction "+_1") (pintype "passive"))
      (node (ref "D7") (pin "1") (pinfunction "A_1") (pintype "passive"))
      (node (ref "D7") (pin "2") (pinfunction "A_2") (pintype "passive"))
      (node (ref "D9") (pin "1") (pinfunction "1_1") (pintype "passive"))
      (node (ref "Q8") (pin "2") (pinfunction "E_2") (pintype "passive"))
      (node (ref "R26") (pin "2") (pinfunction "2_2") (pintype "passive"))
      (node (ref "VBAT2") (pin "1") (pinfunction "1_1") (pintype "passive"))
    )
    (net (code "71") (name "/VNB_CHEAK") (class "Default")
      (node (ref "C34") (pin "2") (pinfunction "2_2") (pintype "passive"))
      (node (ref "R24") (pin "2") (pinfunction "2_2") (pintype "passive"))
      (node (ref "R35") (pin "1") (pinfunction "1_1") (pintype "passive"))
      (node (ref "U7") (pin "70") (pinfunction "PD11(WKUP6)/FOUT0/ADC_IN0/ATIM_BRK1_70") (pintype "passive"))
    )
    (net (code "72") (name "/VNB_CHEAK_EN") (class "Default")
      (node (ref "R36") (pin "1") (pinfunction "1_1") (pintype "passive"))
      (node (ref "U7") (pin "55") (pinfunction "PC9/SEG18/ADC_IN14/SPI2_MISO_55") (pintype "passive"))
    )
    (net (code "73") (name "/WY_POW") (class "Default")
      (node (ref "C10") (pin "1") (pinfunction "1_1") (pintype "passive"))
      (node (ref "C64") (pin "1") (pinfunction "1_1") (pintype "passive"))
      (node (ref "J3") (pin "1") (pinfunction "1_1") (pintype "passive"))
      (node (ref "POW") (pin "1") (pinfunction "1_1") (pintype "passive"))
      (node (ref "R29") (pin "1") (pinfunction "1_1") (pintype "passive"))
      (node (ref "R30") (pin "1") (pinfunction "1_1") (pintype "passive"))
      (node (ref "R97") (pin "2") (pinfunction "2_2") (pintype "passive"))
      (node (ref "U20") (pin "1") (pinfunction "VDDIO_1") (pintype "passive"))
      (node (ref "U20") (pin "3") (pinfunction "VDD_3") (pintype "passive"))
      (node (ref "U7") (pin "5") (pinfunction "PA15/WKUP0/SVS/COMP3_OUT_5") (pintype "passive"))
    )
    (net (code "74") (name "/WY_SCL") (class "Default")
      (node (ref "C39") (pin "2") (pinfunction "2_2") (pintype "passive"))
      (node (ref "J3") (pin "3") (pinfunction "3_3") (pintype "passive"))
      (node (ref "R29") (pin "2") (pinfunction "2_2") (pintype "passive"))
      (node (ref "SCL") (pin "1") (pinfunction "1_1") (pintype "passive"))
      (node (ref "U20") (pin "5") (pinfunction "SCL_5") (pintype "passive"))
      (node (ref "U7") (pin "2") (pinfunction "PE9/CAN_TX/ADC_IN19_2") (pintype "passive"))
    )
    (net (code "75") (name "/WY_SDA") (class "Default")
      (node (ref "C45") (pin "1") (pinfunction "1_1") (pintype "passive"))
      (node (ref "J3") (pin "2") (pinfunction "2_2") (pintype "passive"))
      (node (ref "R30") (pin "2") (pinfunction "2_2") (pintype "passive"))
      (node (ref "SDA") (pin "1") (pinfunction "1_1") (pintype "passive"))
      (node (ref "U20") (pin "6") (pinfunction "SDA_6") (pintype "passive"))
      (node (ref "U7") (pin "1") (pinfunction "PD10/CAN_RX/ADC_IN18_1") (pintype "passive"))
    )
    (net (code "76") (name "/X1") (class "Default")
      (node (ref "U7") (pin "34") (pinfunction "PB13/SEG11/UART1_RX/LPUART1_RX_34") (pintype "passive"))
    )
    (net (code "77") (name "/XT1") (class "Default")
      (node (ref "C28") (pin "2") (pinfunction "2_2") (pintype "passive"))
      (node (ref "U7") (pin "61") (pinfunction "XT32KI_61") (pintype "passive"))
      (node (ref "Y2") (pin "1") (pinfunction "1_1") (pintype "passive"))
    )
    (net (code "78") (name "/XT2") (class "Default")
      (node (ref "C7") (pin "2") (pinfunction "2_2") (pintype "passive"))
      (node (ref "U7") (pin "60") (pinfunction "XT32KO_60") (pintype "passive"))
      (node (ref "Y2") (pin "2") (pinfunction "2_2") (pintype "passive"))
    )
    (net (code "79") (name "3.6V") (class "Default")
      (node (ref "C14") (pin "1") (pinfunction "1_1") (pintype "passive"))
      (node (ref "C9") (pin "1") (pinfunction "1_1") (pintype "passive"))
      (node (ref "D3") (pin "2") (pinfunction "2_2") (pintype "passive"))
      (node (ref "D7") (pin "3") (pinfunction "C_3") (pintype "passive"))
      (node (ref "U3") (pin "2") (pinfunction "Vin_2") (pintype "passive"))
      (node (ref "VIN2") (pin "1") (pinfunction "1_1") (pintype "passive"))
    )
    (net (code "80") (name "5V") (class "Default")
      (node (ref "C12") (pin "1") (pinfunction "1_1") (pintype "passive"))
      (node (ref "C35") (pin "1") (pinfunction "1_1") (pintype "passive"))
      (node (ref "D3") (pin "1") (pinfunction "1_1") (pintype "passive"))
      (node (ref "D8") (pin "1") (pinfunction "1_1") (pintype "passive"))
      (node (ref "R42") (pin "2") (pinfunction "2_2") (pintype "passive"))
      (node (ref "U2") (pin "3") (pinfunction "Vout_3") (pintype "passive"))
      (node (ref "U8") (pin "1") (pinfunction "VM_1") (pintype "passive"))
      (node (ref "VIN3") (pin "1") (pinfunction "1_1") (pintype "passive"))
    )
    (net (code "81") (name "EARTH") (class "Default")
      (node (ref "C29") (pin "1") (pinfunction "1_1") (pintype "passive"))
    )
    (net (code "82") (name "GND") (class "Default")
      (node (ref "BT1") (pin "2") (pinfunction "-_2") (pintype "passive"))
      (node (ref "BT2") (pin "2") (pinfunction "-_2") (pintype "passive"))
      (node (ref "C10") (pin "2") (pinfunction "2_2") (pintype "passive"))
      (node (ref "C11") (pin "2") (pinfunction "2_2") (pintype "passive"))
      (node (ref "C13") (pin "1") (pinfunction "1_1") (pintype "passive"))
      (node (ref "C14") (pin "2") (pinfunction "2_2") (pintype "passive"))
      (node (ref "C15") (pin "2") (pinfunction "2_2") (pintype "passive"))
      (node (ref "C16") (pin "2") (pinfunction "2_2") (pintype "passive"))
      (node (ref "C17") (pin "2") (pinfunction "2_2") (pintype "passive"))
      (node (ref "C18") (pin "2") (pinfunction "2_2") (pintype "passive"))
      (node (ref "C19") (pin "2") (pinfunction "2_2") (pintype "passive"))
      (node (ref "C20") (pin "2") (pinfunction "2_2") (pintype "passive"))
      (node (ref "C21") (pin "2") (pinfunction "2_2") (pintype "passive"))
      (node (ref "C23") (pin "2") (pinfunction "2_2") (pintype "passive"))
      (node (ref "C28") (pin "1") (pinfunction "1_1") (pintype "passive"))
      (node (ref "C29") (pin "2") (pinfunction "2_2") (pintype "passive"))
      (node (ref "C3") (pin "2") (pinfunction "2_2") (pintype "passive"))
      (node (ref "C30") (pin "2") (pinfunction "2_2") (pintype "passive"))
      (node (ref "C31") (pin "2") (pinfunction "2_2") (pintype "passive"))
      (node (ref "C34") (pin "1") (pinfunction "1_1") (pintype "passive"))
      (node (ref "C35") (pin "2") (pinfunction "2_2") (pintype "passive"))
      (node (ref "C36") (pin "2") (pinfunction "2_2") (pintype "passive"))
      (node (ref "C38") (pin "2") (pinfunction "2_2") (pintype "passive"))
      (node (ref "C39") (pin "1") (pinfunction "1_1") (pintype "passive"))
      (node (ref "C4") (pin "2") (pinfunction "2_2") (pintype "passive"))
      (node (ref "C40") (pin "1") (pinfunction "1_1") (pintype "passive"))
      (node (ref "C41") (pin "2") (pinfunction "2_2") (pintype "passive"))
      (node (ref "C42") (pin "2") (pinfunction "2_2") (pintype "passive"))
      (node (ref "C44") (pin "1") (pinfunction "1_1") (pintype "passive"))
      (node (ref "C45") (pin "2") (pinfunction "2_2") (pintype "passive"))
      (node (ref "C46") (pin "1") (pinfunction "1_1") (pintype "passive"))
      (node (ref "C47") (pin "1") (pinfunction "1_1") (pintype "passive"))
      (node (ref "C48") (pin "1") (pinfunction "1_1") (pintype "passive"))
      (node (ref "C49") (pin "1") (pinfunction "1_1") (pintype "passive"))
      (node (ref "C5") (pin "2") (pinfunction "2_2") (pintype "passive"))
      (node (ref "C50") (pin "2") (pinfunction "2_2") (pintype "passive"))
      (node (ref "C51") (pin "2") (pinfunction "2_2") (pintype "passive"))
      (node (ref "C53") (pin "2") (pinfunction "2_2") (pintype "passive"))
      (node (ref "C59") (pin "2") (pinfunction "2_2") (pintype "passive"))
      (node (ref "C6") (pin "2") (pinfunction "2_2") (pintype "passive"))
      (node (ref "C60") (pin "2") (pinfunction "2_2") (pintype "passive"))
      (node (ref "C64") (pin "2") (pinfunction "2_2") (pintype "passive"))
      (node (ref "C7") (pin "1") (pinfunction "1_1") (pintype "passive"))
      (node (ref "C8") (pin "2") (pinfunction "2_2") (pintype "passive"))
      (node (ref "C9") (pin "2") (pinfunction "2_2") (pintype "passive"))
      (node (ref "FB2") (pin "1") (pinfunction "1_1") (pintype "passive"))
      (node (ref "GND") (pin "1") (pinfunction "1_1") (pintype "passive"))
      (node (ref "J3") (pin "4") (pinfunction "4_4") (pintype "passive"))
      (node (ref "J3") (pin "5") (pinfunction "5_5") (pintype "passive"))
      (node (ref "J3") (pin "6") (pinfunction "6_6") (pintype "passive"))
      (node (ref "J6") (pin "4") (pinfunction "4_4") (pintype "passive"))
      (node (ref "J6") (pin "5") (pinfunction "5_5") (pintype "passive"))
      (node (ref "J6") (pin "6") (pinfunction "6_6") (pintype "passive"))
      (node (ref "J8") (pin "4") (pinfunction "4_4") (pintype "passive"))
      (node (ref "J9") (pin "1") (pinfunction "1_1") (pintype "passive"))
      (node (ref "P2") (pin "1") (pinfunction "1_1") (pintype "passive"))
      (node (ref "P2") (pin "6") (pinfunction "6_6") (pintype "passive"))
      (node (ref "P2") (pin "7") (pinfunction "7_7") (pintype "passive"))
      (node (ref "Q11") (pin "2") (pinfunction "E_2") (pintype "passive"))
      (node (ref "Q14") (pin "2") (pinfunction "E_2") (pintype "passive"))
      (node (ref "Q17") (pin "3") (pintype "passive"))
      (node (ref "Q20") (pin "2") (pinfunction "E_2") (pintype "passive"))
      (node (ref "Q22") (pin "3") (pinfunction "C_3") (pintype "passive"))
      (node (ref "Q3") (pin "2") (pinfunction "E_2") (pintype "passive"))
      (node (ref "Q7") (pin "2") (pinfunction "E_2") (pintype "passive"))
      (node (ref "Q9") (pin "3") (pinfunction "C_3") (pintype "passive"))
      (node (ref "R13") (pin "2") (pinfunction "2_2") (pintype "passive"))
      (node (ref "R35") (pin "2") (pinfunction "2_2") (pintype "passive"))
      (node (ref "R5") (pin "1") (pinfunction "1_1") (pintype "passive"))
      (node (ref "R54") (pin "1") (pinfunction "1_1") (pintype "passive"))
      (node (ref "R96") (pin "2") (pinfunction "2_2") (pintype "passive"))
      (node (ref "S1") (pin "2") (pinfunction "2_2") (pintype "passive"))
      (node (ref "S2") (pin "2") (pinfunction "2_2") (pintype "passive"))
      (node (ref "TVS2") (pin "2") (pinfunction "2_2") (pintype "passive"))
      (node (ref "U1") (pin "4") (pinfunction "VSS_4") (pintype "passive"))
      (node (ref "U2") (pin "1") (pinfunction "GND_1") (pintype "passive"))
      (node (ref "U20") (pin "2") (pinfunction "GND_2") (pintype "passive"))
      (node (ref "U3") (pin "1") (pinfunction "GND_1") (pintype "passive"))
      (node (ref "U6") (pin "1") (pinfunction "GND_1") (pintype "passive"))
      (node (ref "U7") (pin "63") (pinfunction "VSS(VSSA)_63") (pintype "passive"))
      (node (ref "U7") (pin "65") (pinfunction "VREFN_65") (pintype "passive"))
      (node (ref "U8") (pin "4") (pinfunction "GND_4") (pintype "passive"))
      (node (ref "U8") (pin "9") (pinfunction "Pad_9") (pintype "passive"))
    )
    (net (code "83") (name "GPRS_3.6V") (class "Default")
      (node (ref "C20") (pin "1") (pinfunction "1_1") (pintype "passive"))
      (node (ref "C3") (pin "1") (pinfunction "1_1") (pintype "passive"))
      (node (ref "C41") (pin "1") (pinfunction "1_1") (pintype "passive"))
      (node (ref "C42") (pin "1") (pinfunction "1_1") (pintype "passive"))
      (node (ref "C51") (pin "1") (pinfunction "1_1") (pintype "passive"))
      (node (ref "C53") (pin "1") (pinfunction "1_1") (pintype "passive"))
      (node (ref "Q15") (pin "3") (pinfunction "D_3") (pintype "passive"))
    )
    (net (code "84") (name "Net-(B1-+)") (class "Default")
      (node (ref "B1") (pin "1") (pinfunction "+_1") (pintype "passive"))
      (node (ref "R27") (pin "1") (pinfunction "1_1") (pintype "passive"))
    )
    (net (code "85") (name "Net-(B1--)") (class "Default")
      (node (ref "B1") (pin "2") (pinfunction "-_2") (pintype "passive"))
      (node (ref "Q11") (pin "3") (pinfunction "C_3") (pintype "passive"))
    )
    (net (code "86") (name "Net-(C12-Pad2)") (class "Default")
      (node (ref "C12") (pin "2") (pinfunction "2_2") (pintype "passive"))
      (node (ref "C50") (pin "1") (pinfunction "1_1") (pintype "passive"))
    )
    (net (code "87") (name "Net-(D1-Pad2)") (class "Default")
      (node (ref "D1") (pin "2") (pinfunction "2_2") (pintype "passive"))
      (node (ref "R37") (pin "2") (pinfunction "2_2") (pintype "passive"))
    )
    (net (code "88") (name "Net-(D5-Pad2)") (class "Default")
      (node (ref "D5") (pin "2") (pinfunction "2_2") (pintype "passive"))
      (node (ref "R15") (pin "2") (pinfunction "2_2") (pintype "passive"))
    )
    (net (code "89") (name "Net-(D6-Pad1)") (class "Default")
      (node (ref "D6") (pin "1") (pinfunction "1_1") (pintype "passive"))
      (node (ref "R19") (pin "2") (pinfunction "2_2") (pintype "passive"))
    )
    (net (code "90") (name "Net-(D10-A-Pad1)") (class "Default")
      (node (ref "D10") (pin "1") (pinfunction "A_1") (pintype "passive"))
      (node (ref "D10") (pin "2") (pinfunction "A_2") (pintype "passive"))
      (node (ref "FB1") (pin "2") (pinfunction "2_2") (pintype "passive"))
    )
    (net (code "91") (name "Net-(D13-Pad2)") (class "Default")
      (node (ref "D13") (pin "2") (pinfunction "2_2") (pintype "passive"))
      (node (ref "Q17") (pin "1") (pintype "passive"))
      (node (ref "R75") (pin "2") (pinfunction "2_2") (pintype "passive"))
    )
    (net (code "92") (name "Net-(J8-Pad1)") (class "Default")
      (node (ref "J8") (pin "1") (pinfunction "1_1") (pintype "passive"))
      (node (ref "R95") (pin "2") (pinfunction "2_2") (pintype "passive"))
    )
    (net (code "93") (name "Net-(P2-Pad2)") (class "Default")
      (node (ref "P2") (pin "2") (pinfunction "2_2") (pintype "passive"))
      (node (ref "R61") (pin "2") (pinfunction "2_2") (pintype "passive"))
      (node (ref "R62") (pin "2") (pinfunction "2_2") (pintype "passive"))
      (node (ref "TXD") (pin "1") (pinfunction "1_1") (pintype "passive"))
    )
    (net (code "94") (name "Net-(P2-Pad4)") (class "Default")
      (node (ref "P2") (pin "4") (pinfunction "4_4") (pintype "passive"))
      (node (ref "R60") (pin "2") (pinfunction "2_2") (pintype "passive"))
      (node (ref "RXD") (pin "1") (pinfunction "1_1") (pintype "passive"))
    )
    (net (code "95") (name "Net-(Q1-B)") (class "Default")
      (node (ref "Q1") (pin "1") (pinfunction "B_1") (pintype "passive"))
      (node (ref "R1") (pin "2") (pinfunction "2_2") (pintype "passive"))
    )
    (net (code "96") (name "Net-(Q1-C)") (class "Default")
      (node (ref "Q1") (pin "3") (pinfunction "C_3") (pintype "passive"))
      (node (ref "R9") (pin "1") (pinfunction "1_1") (pintype "passive"))
    )
    (net (code "97") (name "Net-(Q3-B)") (class "Default")
      (node (ref "Q3") (pin "1") (pinfunction "B_1") (pintype "passive"))
      (node (ref "R14") (pin "2") (pinfunction "2_2") (pintype "passive"))
    )
    (net (code "98") (name "Net-(Q3-C)") (class "Default")
      (node (ref "Q3") (pin "3") (pinfunction "C_3") (pintype "passive"))
      (node (ref "R1") (pin "1") (pinfunction "1_1") (pintype "passive"))
      (node (ref "R10") (pin "1") (pinfunction "1_1") (pintype "passive"))
    )
    (net (code "99") (name "Net-(Q4-B)") (class "Default")
      (node (ref "Q4") (pin "1") (pinfunction "B_1") (pintype "passive"))
      (node (ref "R25") (pin "1") (pinfunction "1_1") (pintype "passive"))
    )
    (net (code "100") (name "Net-(Q4-C)") (class "Default")
      (node (ref "D5") (pin "1") (pinfunction "1_1") (pintype "passive"))
      (node (ref "Q4") (pin "3") (pinfunction "C_3") (pintype "passive"))
      (node (ref "R16") (pin "2") (pinfunction "2_2") (pintype "passive"))
    )
    (net (code "101") (name "Net-(Q6-B)") (class "Default")
      (node (ref "Q6") (pin "1") (pinfunction "B_1") (pintype "passive"))
      (node (ref "R34") (pin "1") (pinfunction "1_1") (pintype "passive"))
      (node (ref "R41") (pin "2") (pinfunction "2_2") (pintype "passive"))
    )
    (net (code "102") (name "Net-(Q6-C)") (class "Default")
      (node (ref "Q6") (pin "3") (pinfunction "C_3") (pintype "passive"))
      (node (ref "R53") (pin "2") (pinfunction "2_2") (pintype "passive"))
    )
    (net (code "103") (name "Net-(Q7-B)") (class "Default")
      (node (ref "C11") (pin "1") (pinfunction "1_1") (pintype "passive"))
      (node (ref "Q7") (pin "1") (pinfunction "B_1") (pintype "passive"))
      (node (ref "R19") (pin "1") (pinfunction "1_1") (pintype "passive"))
      (node (ref "R5") (pin "2") (pinfunction "2_2") (pintype "passive"))
    )
    (net (code "104") (name "Net-(Q8-B)") (class "Default")
      (node (ref "Q8") (pin "1") (pinfunction "B_1") (pintype "passive"))
      (node (ref "R33") (pin "2") (pinfunction "2_2") (pintype "passive"))
    )
    (net (code "105") (name "Net-(Q8-C)") (class "Default")
      (node (ref "Q8") (pin "3") (pinfunction "C_3") (pintype "passive"))
      (node (ref "R24") (pin "1") (pinfunction "1_1") (pintype "passive"))
    )
    (net (code "106") (name "Net-(Q9-B)") (class "Default")
      (node (ref "Q9") (pin "1") (pinfunction "B_1") (pintype "passive"))
      (node (ref "R3") (pin "2") (pinfunction "2_2") (pintype "passive"))
    )
    (net (code "107") (name "Net-(Q9-E)") (class "Default")
      (node (ref "Q9") (pin "2") (pinfunction "E_2") (pintype "passive"))
      (node (ref "R15") (pin "1") (pinfunction "1_1") (pintype "passive"))
    )
    (net (code "108") (name "Net-(Q10-B)") (class "Default")
      (node (ref "Q10") (pin "1") (pinfunction "B_1") (pintype "passive"))
      (node (ref "R12") (pin "2") (pinfunction "2_2") (pintype "passive"))
    )
    (net (code "109") (name "Net-(Q10-C)") (class "Default")
      (node (ref "C36") (pin "1") (pinfunction "1_1") (pintype "passive"))
      (node (ref "Q10") (pin "3") (pinfunction "C_3") (pintype "passive"))
      (node (ref "U1") (pin "7") (pinfunction "HOLD#_7") (pintype "passive"))
      (node (ref "U1") (pin "8") (pinfunction "VDD_8") (pintype "passive"))
    )
    (net (code "110") (name "Net-(Q11-B)") (class "Default")
      (node (ref "Q11") (pin "1") (pinfunction "B_1") (pintype "passive"))
      (node (ref "R38") (pin "2") (pinfunction "2_2") (pintype "passive"))
    )
    (net (code "111") (name "Net-(Q14-B)") (class "Default")
      (node (ref "Q14") (pin "1") (pinfunction "B_1") (pintype "passive"))
      (node (ref "R36") (pin "2") (pinfunction "2_2") (pintype "passive"))
    )
    (net (code "112") (name "Net-(Q14-C)") (class "Default")
      (node (ref "Q14") (pin "3") (pinfunction "C_3") (pintype "passive"))
      (node (ref "R26") (pin "1") (pinfunction "1_1") (pintype "passive"))
      (node (ref "R33") (pin "1") (pinfunction "1_1") (pintype "passive"))
    )
    (net (code "113") (name "Net-(Q15-G)") (class "Default")
      (node (ref "Q15") (pin "1") (pinfunction "G_1") (pintype "passive"))
      (node (ref "R18") (pin "2") (pinfunction "2_2") (pintype "passive"))
      (node (ref "R6") (pin "1") (pinfunction "1_1") (pintype "passive"))
    )
    (net (code "114") (name "Net-(Q15-S)") (class "Default")
      (node (ref "C21") (pin "1") (pinfunction "1_1") (pintype "passive"))
      (node (ref "Q15") (pin "2") (pinfunction "S_2") (pintype "passive"))
      (node (ref "R50") (pin "2") (pinfunction "2_2") (pintype "passive"))
      (node (ref "R6") (pin "2") (pinfunction "2_2") (pintype "passive"))
      (node (ref "U6") (pin "3") (pinfunction "Vout_3") (pintype "passive"))
    )
    (net (code "115") (name "Net-(Q20-B)") (class "Default")
      (node (ref "Q20") (pin "1") (pinfunction "B_1") (pintype "passive"))
      (node (ref "R53") (pin "1") (pinfunction "1_1") (pintype "passive"))
      (node (ref "R54") (pin "2") (pinfunction "2_2") (pintype "passive"))
    )
    (net (code "116") (name "Net-(Q22-B)") (class "Default")
      (node (ref "Q22") (pin "1") (pinfunction "B_1") (pintype "passive"))
      (node (ref "R61") (pin "1") (pinfunction "1_1") (pintype "passive"))
    )
    (net (code "117") (name "Net-(Q22-E)") (class "Default")
      (node (ref "Q22") (pin "2") (pinfunction "E_2") (pintype "passive"))
      (node (ref "R58") (pin "2") (pinfunction "2_2") (pintype "passive"))
      (node (ref "R59") (pin "1") (pinfunction "1_1") (pintype "passive"))
    )
    (net (code "118") (name "Net-(U2-Vin)") (class "Default")
      (node (ref "C4") (pin "1") (pinfunction "1_1") (pintype "passive"))
      (node (ref "D2") (pin "2") (pinfunction "2_2") (pintype "passive"))
      (node (ref "R42") (pin "1") (pinfunction "1_1") (pintype "passive"))
      (node (ref "U2") (pin "2") (pinfunction "Vin_2") (pintype "passive"))
    )
    (net (code "119") (name "Net-(U7-VDD15)") (class "Default")
      (node (ref "C38") (pin "1") (pinfunction "1_1") (pintype "passive"))
      (node (ref "U7") (pin "62") (pinfunction "VDD15_62") (pintype "passive"))
    )
    (net (code "120") (name "Net-(U20-SDO)") (class "Default")
      (node (ref "R96") (pin "1") (pinfunction "1_1") (pintype "passive"))
      (node (ref "R97") (pin "1") (pinfunction "1_1") (pintype "passive"))
      (node (ref "U20") (pin "8") (pinfunction "SDO_8") (pintype "passive"))
    )
    (net (code "121") (name "VCC") (class "Default")
      (node (ref "C13") (pin "2") (pinfunction "2_2") (pintype "passive"))
      (node (ref "C17") (pin "1") (pinfunction "1_1") (pintype "passive"))
      (node (ref "C18") (pin "1") (pinfunction "1_1") (pintype "passive"))
      (node (ref "C30") (pin "1") (pinfunction "1_1") (pintype "passive"))
      (node (ref "C31") (pin "1") (pinfunction "1_1") (pintype "passive"))
      (node (ref "C44") (pin "2") (pinfunction "2_2") (pintype "passive"))
      (node (ref "C48") (pin "2") (pinfunction "2_2") (pintype "passive"))
      (node (ref "C5") (pin "1") (pinfunction "1_1") (pintype "passive"))
      (node (ref "C6") (pin "1") (pinfunction "1_1") (pintype "passive"))
      (node (ref "D1") (pin "1") (pinfunction "1_1") (pintype "passive"))
      (node (ref "J8") (pin "5") (pinfunction "5_5") (pintype "passive"))
      (node (ref "P2") (pin "5") (pinfunction "5_5") (pintype "passive"))
      (node (ref "Q10") (pin "2") (pinfunction "E_2") (pintype "passive"))
      (node (ref "Q4") (pin "2") (pinfunction "E_2") (pintype "passive"))
      (node (ref "Q6") (pin "2") (pinfunction "E_2") (pintype "passive"))
      (node (ref "R27") (pin "2") (pinfunction "2_2") (pintype "passive"))
      (node (ref "R34") (pin "2") (pinfunction "2_2") (pintype "passive"))
      (node (ref "R59") (pin "2") (pinfunction "2_2") (pintype "passive"))
      (node (ref "R93") (pin "1") (pinfunction "1_1") (pintype "passive"))
      (node (ref "R94") (pin "2") (pinfunction "2_2") (pintype "passive"))
      (node (ref "U3") (pin "3") (pinfunction "Vout_3") (pintype "passive"))
      (node (ref "U7") (pin "64") (pinfunction "VDD(VDDA)_64") (pintype "passive"))
      (node (ref "U7") (pin "66") (pinfunction "VREFP_66") (pintype "passive"))
      (node (ref "U7") (pin "67") (pinfunction "VBAT_67") (pintype "passive"))
      (node (ref "U8") (pin "8") (pinfunction "VCC_8") (pintype "passive"))
      (node (ref "VCC") (pin "1") (pinfunction "1_1") (pintype "passive"))
    )
    (net (code "122") (name "VIN") (class "Default")
      (node (ref "BT1") (pin "1") (pinfunction "+_1") (pintype "passive"))
      (node (ref "D2") (pin "1") (pinfunction "1_1") (pintype "passive"))
      (node (ref "D4") (pin "1") (pinfunction "1_1") (pintype "passive"))
      (node (ref "Q1") (pin "2") (pinfunction "E_2") (pintype "passive"))
      (node (ref "R10") (pin "2") (pinfunction "2_2") (pintype "passive"))
      (node (ref "VIN1") (pin "1") (pinfunction "1_1") (pintype "passive"))
    )
    (net (code "123") (name "VIN_NB") (class "Default")
      (node (ref "C15") (pin "1") (pinfunction "1_1") (pintype "passive"))
      (node (ref "C23") (pin "1") (pinfunction "1_1") (pintype "passive"))
      (node (ref "D4") (pin "2") (pinfunction "2_2") (pintype "passive"))
      (node (ref "D8") (pin "2") (pinfunction "2_2") (pintype "passive"))
      (node (ref "D9") (pin "2") (pinfunction "2_2") (pintype "passive"))
      (node (ref "R50") (pin "1") (pinfunction "1_1") (pintype "passive"))
      (node (ref "U6") (pin "2") (pinfunction "Vin_2") (pintype "passive"))
    )
    (net (code "124") (name "unconnected-(U7-PC1{slash}VDISP3{slash}GPT1_CH2{slash}COMP3_INP2{slash}LUT1_OUT-Pad47)") (class "Default")
      (node (ref "U7") (pin "47") (pinfunction "PC1/VDISP3/GPT1_CH2/COMP3_INP2/LUT1_OUT_47") (pintype "passive"))
    )
    (net (code "125") (name "unconnected-(U7-PD3{slash}SEG25{slash}SPI1_SCK{slash}ADC_IN2{slash}GPT2_CH4-Pad74)") (class "Default")
      (node (ref "U7") (pin "74") (pinfunction "PD3/SEG25/SPI1_SCK/ADC_IN2/GPT2_CH4_74") (pintype "passive"))
    )
    (net (code "126") (name "unconnected-(U20-CSB-Pad7)") (class "Default")
      (node (ref "U20") (pin "7") (pinfunction "CSB_7") (pintype "passive"))
    )
    (net (code "127") (name "unconnected-(U20-NC-Pad4)") (class "Default")
      (node (ref "U20") (pin "4") (pinfunction "NC_4") (pintype "passive+no_connect"))
    )
  )
)
